# Nixie_Clock.net
KiCad netlist of a schematic drawn in EAGLE
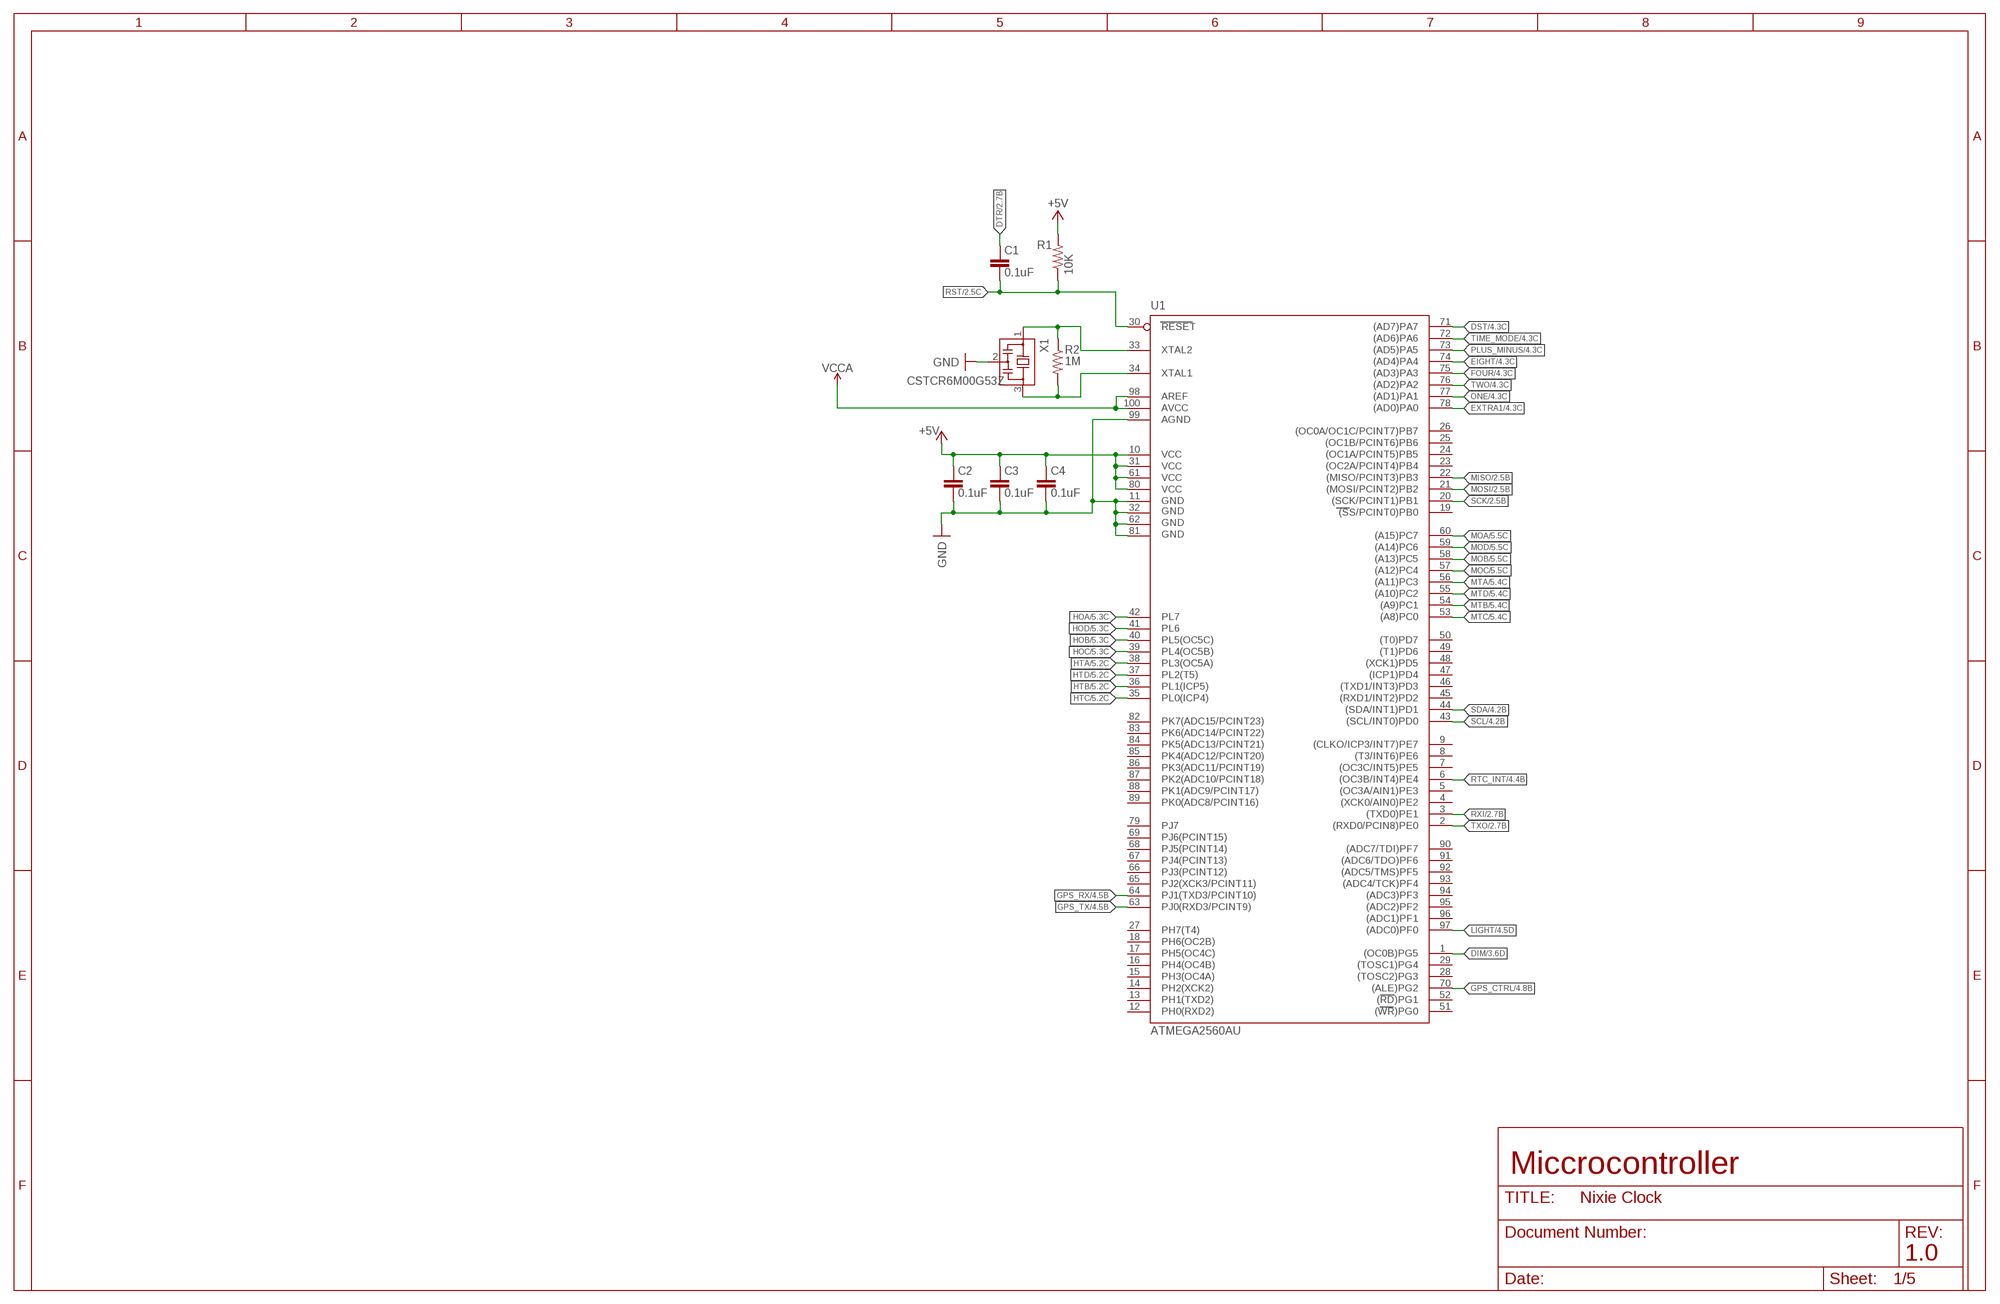
[diagram p0: schematic, sheet 1]
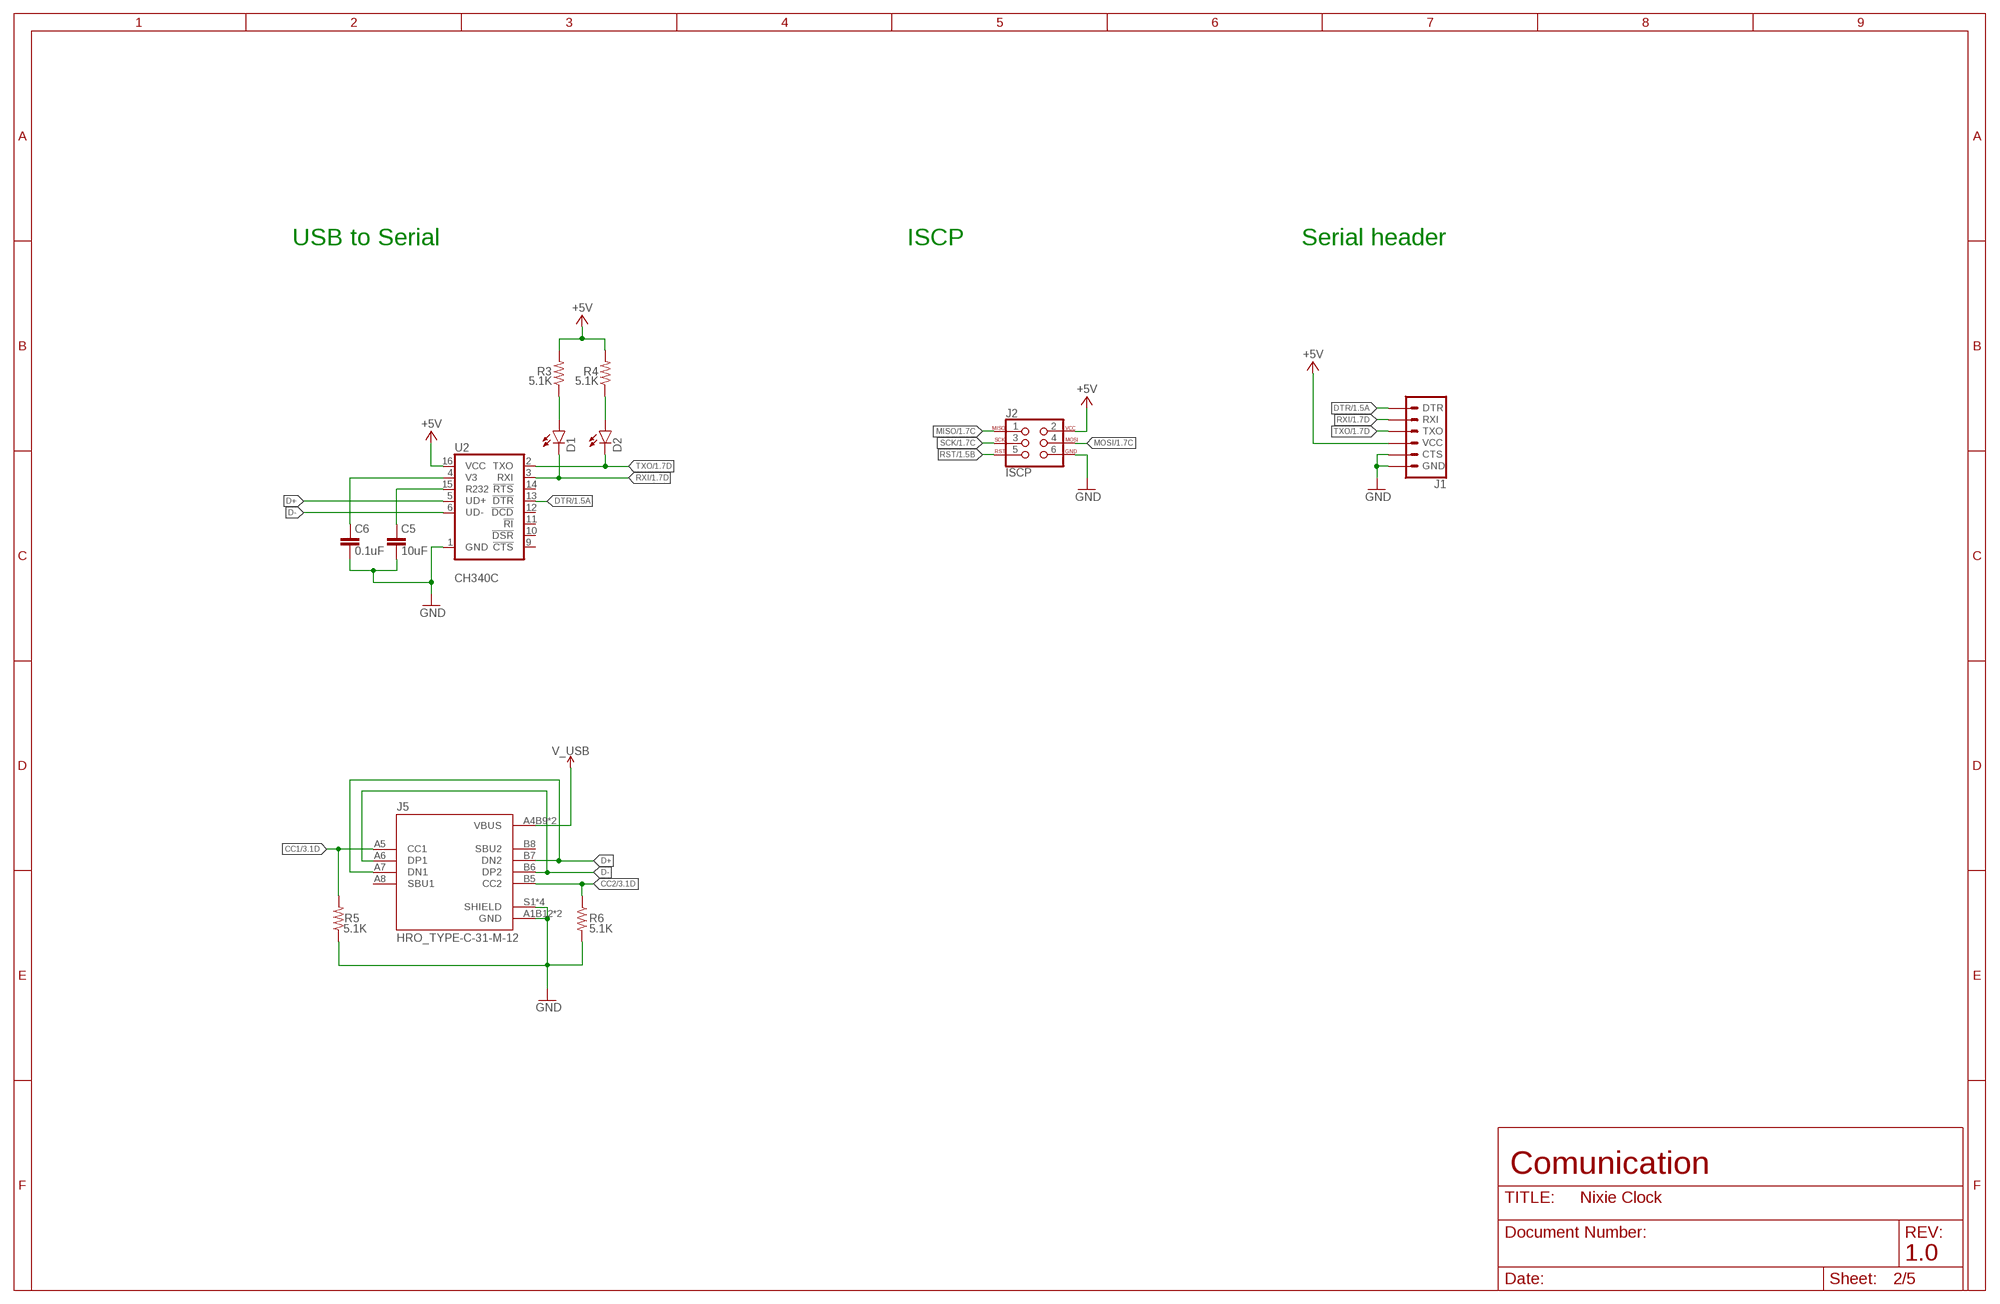
[diagram p1: schematic, sheet 2]
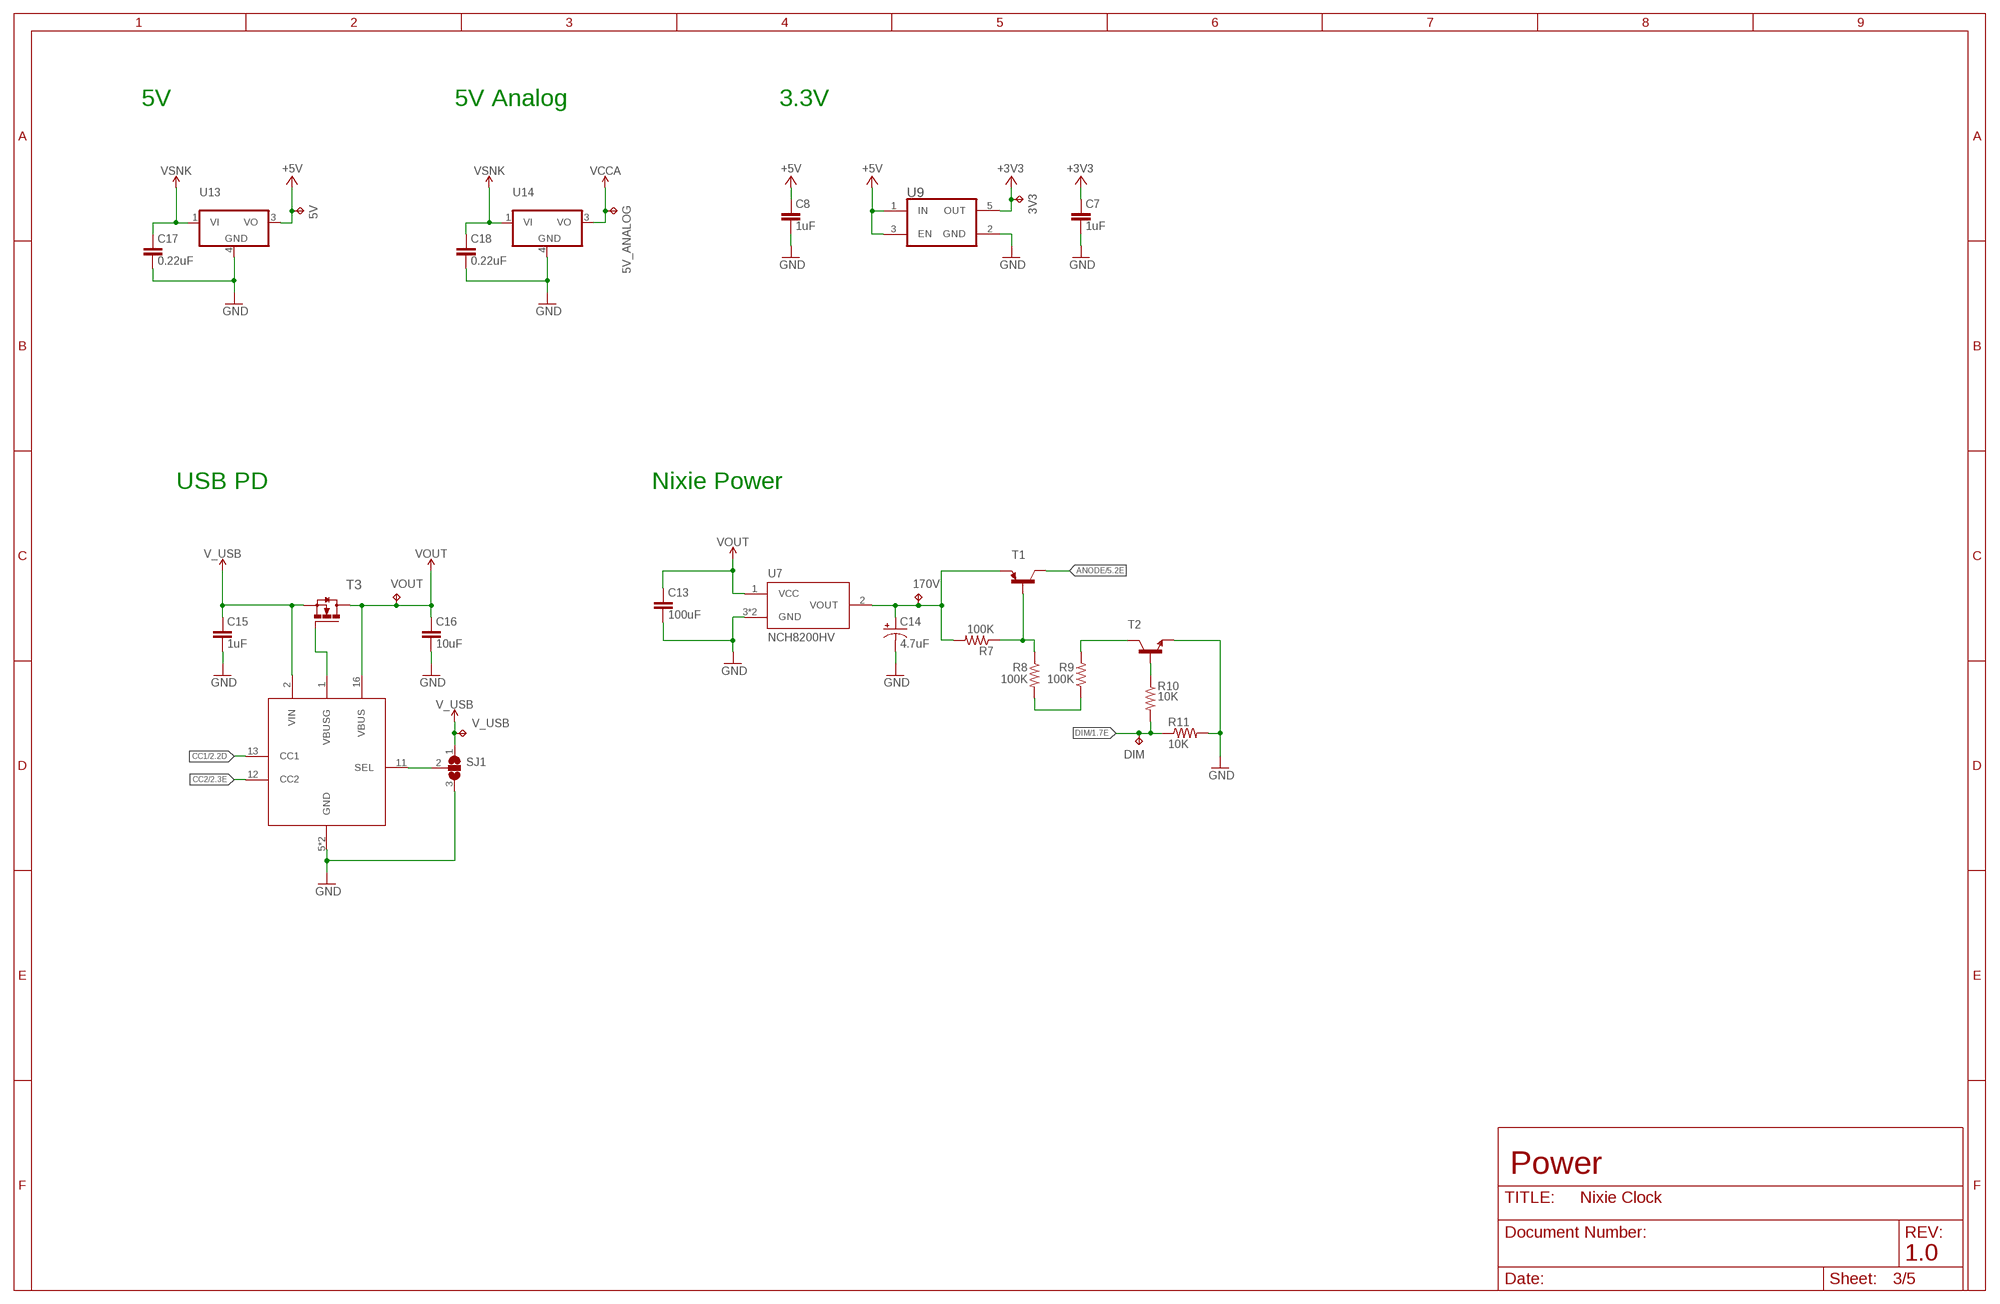
[diagram p2: schematic, sheet 3]
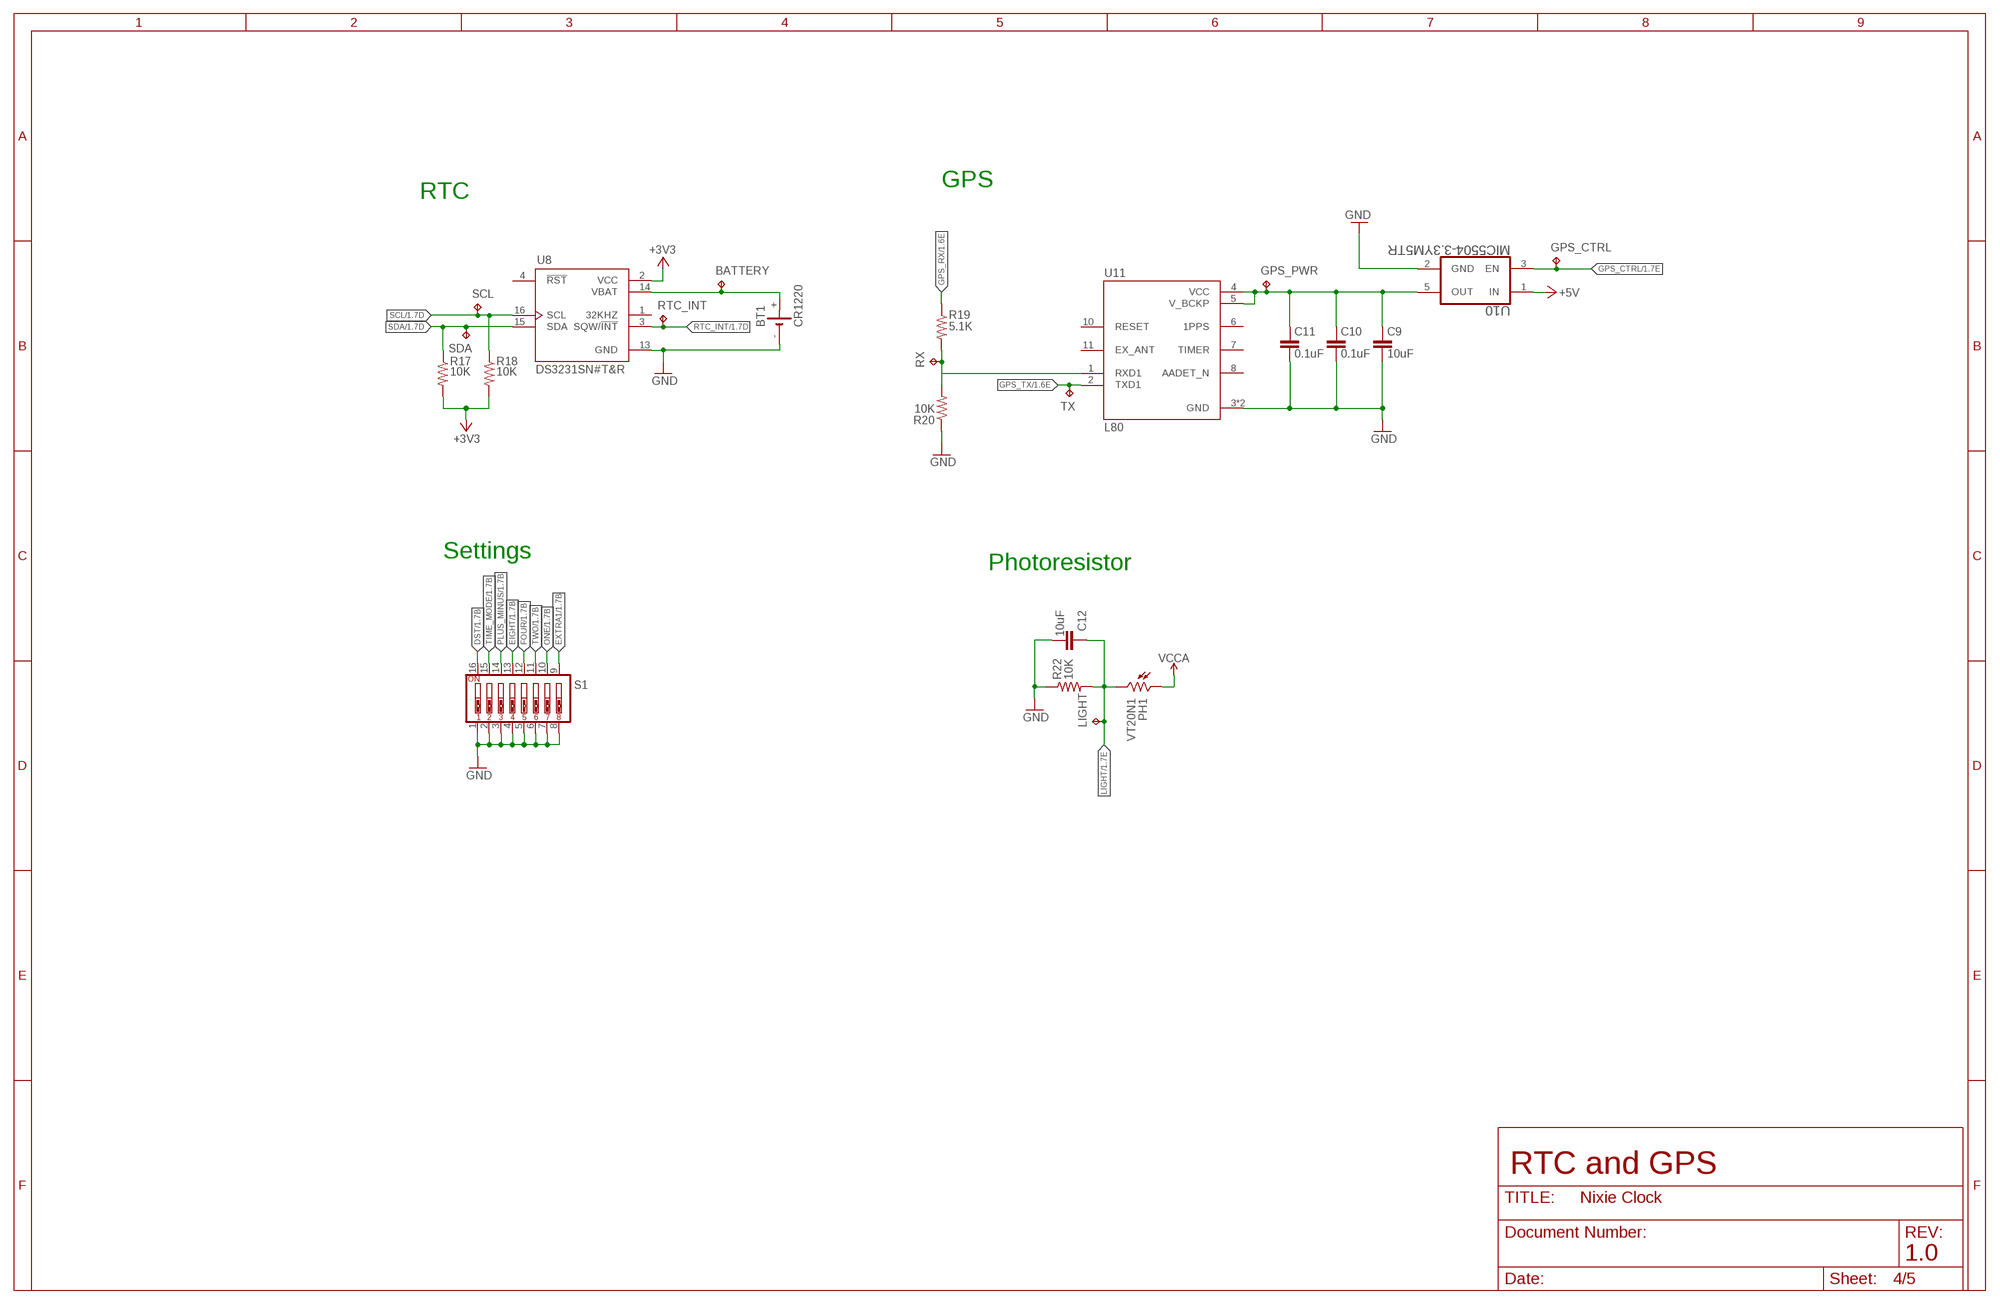
[diagram p3: schematic, sheet 4]
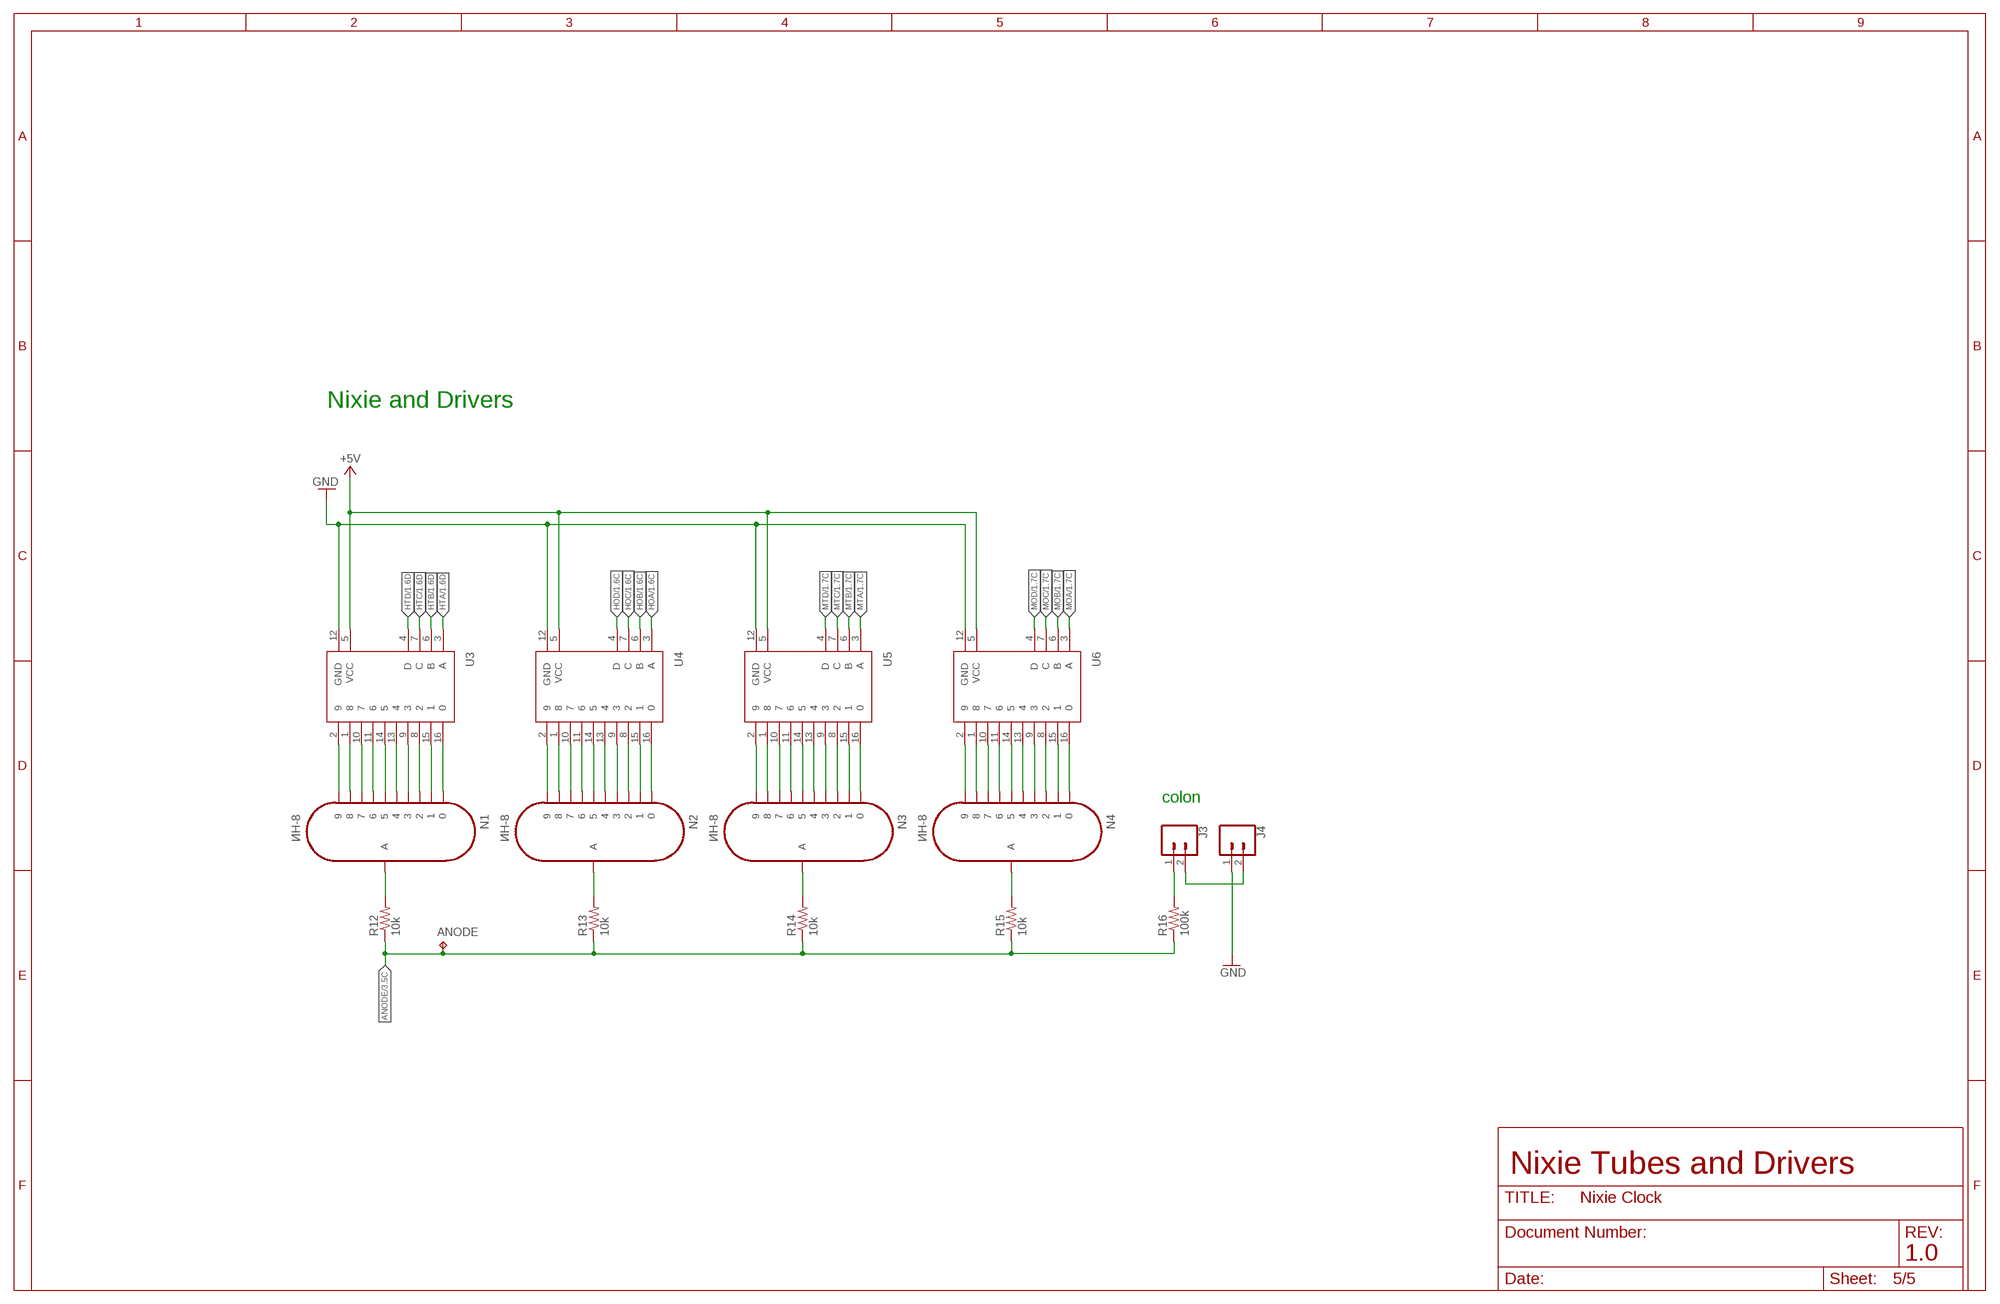
[diagram p4: schematic, sheet 5]

(export (version "E")
  (design (tool "Eeschema 10.0.6"))
  (components
    (comp (ref "BATTERY")
      (value "TPPAD1-13")
      (footprint "eagle-import:P1-13")
      (libsource (lib "eagle-import") (part "TPPAD1-13"))
    )
    (comp (ref "BT1")
      (value "CR1220")
      (footprint "eagle-import:CH291-1220LF")
      (libsource (lib "eagle-import") (part "CH291-1220LF"))
    )
    (comp (ref "C9")
      (value "10uF")
      (footprint "eagle-import:C0603")
      (libsource (lib "eagle-import") (part "C-EUC0603"))
    )
    (comp (ref "C10")
      (value "0.1uF")
      (footprint "eagle-import:C0603")
      (libsource (lib "eagle-import") (part "C-EUC0603"))
    )
    (comp (ref "C11")
      (value "0.1uF")
      (footprint "eagle-import:C0603")
      (libsource (lib "eagle-import") (part "C-EUC0603"))
    )
    (comp (ref "C12")
      (value "10uF")
      (footprint "eagle-import:C0603")
      (libsource (lib "eagle-import") (part "C-EUC0603"))
    )
    (comp (ref "GPS_CTRL")
      (value "TPPAD1-13")
      (footprint "eagle-import:P1-13")
      (libsource (lib "eagle-import") (part "TPPAD1-13"))
    )
    (comp (ref "GPS_PWR")
      (value "TPPAD1-13")
      (footprint "eagle-import:P1-13")
      (libsource (lib "eagle-import") (part "TPPAD1-13"))
    )
    (comp (ref "LIGHT")
      (value "TPPAD1-13")
      (footprint "eagle-import:P1-13")
      (libsource (lib "eagle-import") (part "TPPAD1-13"))
    )
    (comp (ref "PH1")
      (value "VT20N1")
      (footprint "eagle-import:TO46-VT200")
      (libsource (lib "eagle-import") (part "VT20N1"))
    )
    (comp (ref "R17")
      (value "10K")
      (footprint "eagle-import:R0603")
      (libsource (lib "eagle-import") (part "R-US_R0603"))
    )
    (comp (ref "R18")
      (value "10K")
      (footprint "eagle-import:R0603")
      (libsource (lib "eagle-import") (part "R-US_R0603"))
    )
    (comp (ref "R19")
      (value "5.1K")
      (footprint "eagle-import:R0603")
      (libsource (lib "eagle-import") (part "R-US_R0603"))
    )
    (comp (ref "R20")
      (value "10K")
      (footprint "eagle-import:R0603")
      (libsource (lib "eagle-import") (part "R-US_R0603"))
    )
    (comp (ref "R22")
      (value "10K")
      (footprint "eagle-import:R0603")
      (libsource (lib "eagle-import") (part "R-US_R0603"))
    )
    (comp (ref "RTC_INT")
      (value "TPPAD1-13")
      (footprint "eagle-import:P1-13")
      (libsource (lib "eagle-import") (part "TPPAD1-13"))
    )
    (comp (ref "RX")
      (value "TPPAD1-13")
      (footprint "eagle-import:P1-13")
      (libsource (lib "eagle-import") (part "TPPAD1-13"))
    )
    (comp (ref "S1")
      (value "SW_DIP-8")
      (footprint "eagle-import:EDG-08")
      (libsource (lib "eagle-import") (part "SW_DIP-8"))
    )
    (comp (ref "SCL")
      (value "TPPAD1-13")
      (footprint "eagle-import:P1-13")
      (libsource (lib "eagle-import") (part "TPPAD1-13"))
    )
    (comp (ref "SDA")
      (value "TPPAD1-13")
      (footprint "eagle-import:P1-13")
      (libsource (lib "eagle-import") (part "TPPAD1-13"))
    )
    (comp (ref "TX")
      (value "TPPAD1-13")
      (footprint "eagle-import:P1-13")
      (libsource (lib "eagle-import") (part "TPPAD1-13"))
    )
    (comp (ref "U8")
      (value "DS3231SN#T&R")
      (footprint "eagle-import:SOIC127P1032X265-16N")
      (fields (field (name "MF") "Maxim Integrated") (field (name "MP") "DS3231SN#T&amp;R"))
      (libsource (lib "eagle-import") (part "DS3231SN#T&R"))
    )
    (comp (ref "U10")
      (value "MIC5504-3.3YM5TR")
      (footprint "eagle-import:SOT95P280X130-5N")
      (fields (field (name "MPN") "MIC5504-3.3YM5-TR"))
      (libsource (lib "eagle-import") (part "MIC5504-3.3YM5TR"))
    )
    (comp (ref "U11")
      (value "L80")
      (footprint "eagle-import:XCVR_L80")
      (fields (field (name "MF") "Quectel") (field (name "MP") "L80-M39"))
      (libsource (lib "eagle-import") (part "L80"))
    )
    (comp (ref "ANODE")
      (value "TPPAD1-13")
      (footprint "eagle-import:P1-13")
      (libsource (lib "eagle-import") (part "TPPAD1-13"))
    )
    (comp (ref "J3")
      (value "CONN_02LOCK_LONGPADS")
      (footprint "eagle-import:1X02_LOCK_LONGPADS")
      (libsource (lib "eagle-import") (part "CONN_02LOCK_LONGPADS"))
    )
    (comp (ref "J4")
      (value "CONN_02LOCK_LONGPADS")
      (footprint "eagle-import:1X02_LOCK_LONGPADS")
      (libsource (lib "eagle-import") (part "CONN_02LOCK_LONGPADS"))
    )
    (comp (ref "N1")
      (value "ИН-8")
      (footprint "eagle-import:IN-8_SOCKET")
      (libsource (lib "eagle-import") (part "IN-8IN-8_SOCKET"))
    )
    (comp (ref "N2")
      (value "ИН-8")
      (footprint "eagle-import:IN-8_SOCKET")
      (libsource (lib "eagle-import") (part "IN-8IN-8_SOCKET"))
    )
    (comp (ref "N3")
      (value "ИН-8")
      (footprint "eagle-import:IN-8_SOCKET")
      (libsource (lib "eagle-import") (part "IN-8IN-8_SOCKET"))
    )
    (comp (ref "N4")
      (value "ИН-8")
      (footprint "eagle-import:IN-8_SOCKET")
      (libsource (lib "eagle-import") (part "IN-8IN-8_SOCKET"))
    )
    (comp (ref "R12")
      (value "10k")
      (footprint "eagle-import:M0805")
      (libsource (lib "eagle-import") (part "R-US_M0805"))
    )
    (comp (ref "R13")
      (value "10k")
      (footprint "eagle-import:M0805")
      (libsource (lib "eagle-import") (part "R-US_M0805"))
    )
    (comp (ref "R14")
      (value "10k")
      (footprint "eagle-import:M0805")
      (libsource (lib "eagle-import") (part "R-US_M0805"))
    )
    (comp (ref "R15")
      (value "10k")
      (footprint "eagle-import:M0805")
      (libsource (lib "eagle-import") (part "R-US_M0805"))
    )
    (comp (ref "R16")
      (value "100k")
      (footprint "eagle-import:R0603")
      (libsource (lib "eagle-import") (part "R-US_R0603"))
    )
    (comp (ref "U3")
      (value "K155ID1")
      (footprint "eagle-import:DIL16-KIT")
      (libsource (lib "eagle-import") (part "K155ID1"))
    )
    (comp (ref "U4")
      (value "K155ID1")
      (footprint "eagle-import:DIL16-KIT")
      (libsource (lib "eagle-import") (part "K155ID1"))
    )
    (comp (ref "U5")
      (value "K155ID1")
      (footprint "eagle-import:DIL16-KIT")
      (libsource (lib "eagle-import") (part "K155ID1"))
    )
    (comp (ref "U6")
      (value "K155ID1")
      (footprint "eagle-import:DIL16-KIT")
      (libsource (lib "eagle-import") (part "K155ID1"))
    )
    (comp (ref "C5")
      (value "10uF")
      (footprint "eagle-import:C0603")
      (libsource (lib "eagle-import") (part "C-EUC0603"))
    )
    (comp (ref "C6")
      (value "0.1uF")
      (footprint "eagle-import:C0603")
      (libsource (lib "eagle-import") (part "C-EUC0603"))
    )
    (comp (ref "D1")
      (value "LEDCHIP-LED0603")
      (footprint "eagle-import:CHIP-LED0603")
      (libsource (lib "eagle-import") (part "LEDCHIP-LED0603"))
    )
    (comp (ref "D2")
      (value "LEDCHIP-LED0603")
      (footprint "eagle-import:CHIP-LED0603")
      (libsource (lib "eagle-import") (part "LEDCHIP-LED0603"))
    )
    (comp (ref "J1")
      (value "6_PIN_SERIAL_TARGETSILK")
      (footprint "eagle-import:6_PIN_SERIAL_TARGET_SIDE_W_SILK")
      (libsource (lib "eagle-import") (part "6_PIN_SERIAL_TARGETSILK"))
    )
    (comp (ref "J2")
      (value "ISCP")
      (footprint "eagle-import:2X3")
      (libsource (lib "eagle-import") (part "AVR_SPI_PROG_3X2PTH"))
    )
    (comp (ref "J5")
      (value "HRO_TYPE-C-31-M-12")
      (footprint "eagle-import:HRO_TYPE-C-31-M-12")
      (fields (field (name "MF") "HRO Electronics Co., Ltd.") (field (name "MP") "TYPE-C-31-M-12"))
      (libsource (lib "eagle-import") (part "HRO_TYPE-C-31-M-12"))
    )
    (comp (ref "R3")
      (value "5.1K")
      (footprint "eagle-import:R0603")
      (libsource (lib "eagle-import") (part "R-US_R0603"))
    )
    (comp (ref "R4")
      (value "5.1K")
      (footprint "eagle-import:R0603")
      (libsource (lib "eagle-import") (part "R-US_R0603"))
    )
    (comp (ref "R5")
      (value "5.1K")
      (footprint "eagle-import:R0603")
      (libsource (lib "eagle-import") (part "R-US_R0603"))
    )
    (comp (ref "R6")
      (value "5.1K")
      (footprint "eagle-import:R0603")
      (libsource (lib "eagle-import") (part "R-US_R0603"))
    )
    (comp (ref "U2")
      (value "CH340C")
      (footprint "eagle-import:SO016")
      (libsource (lib "eagle-import") (part "CH340C"))
    )
    (comp (ref "3V3")
      (value "TPPAD1-13")
      (footprint "eagle-import:P1-13")
      (libsource (lib "eagle-import") (part "TPPAD1-13"))
    )
    (comp (ref "5V")
      (value "TPPAD1-13")
      (footprint "eagle-import:P1-13")
      (libsource (lib "eagle-import") (part "TPPAD1-13"))
    )
    (comp (ref "5V_ANALOG")
      (value "TPPAD1-13")
      (footprint "eagle-import:P1-13")
      (libsource (lib "eagle-import") (part "TPPAD1-13"))
    )
    (comp (ref "170V")
      (value "TPPAD1-13")
      (footprint "eagle-import:P1-13")
      (libsource (lib "eagle-import") (part "TPPAD1-13"))
    )
    (comp (ref "C7")
      (value "1uF")
      (footprint "eagle-import:C0603")
      (libsource (lib "eagle-import") (part "C-EUC0603"))
    )
    (comp (ref "C8")
      (value "1uF")
      (footprint "eagle-import:C0603")
      (libsource (lib "eagle-import") (part "C-EUC0603"))
    )
    (comp (ref "C13")
      (value "100uF")
      (footprint "eagle-import:C0603")
      (libsource (lib "eagle-import") (part "C-EUC0603"))
    )
    (comp (ref "C14")
      (value "4.7uF")
      (footprint "eagle-import:E3,5-8")
      (libsource (lib "eagle-import") (part "CPOL-USE3.5-8"))
    )
    (comp (ref "C15")
      (value "1uF")
      (footprint "eagle-import:C0603")
      (libsource (lib "eagle-import") (part "C-EUC0603"))
    )
    (comp (ref "C16")
      (value "10uF")
      (footprint "eagle-import:C0603")
      (libsource (lib "eagle-import") (part "C-EUC0603"))
    )
    (comp (ref "C17")
      (value "0.22uF")
      (footprint "eagle-import:C0603")
      (libsource (lib "eagle-import") (part "C-EUC0603"))
    )
    (comp (ref "C18")
      (value "0.22uF")
      (footprint "eagle-import:C0603")
      (libsource (lib "eagle-import") (part "C-EUC0603"))
    )
    (comp (ref "DIM")
      (value "TPPAD1-13")
      (footprint "eagle-import:P1-13")
      (libsource (lib "eagle-import") (part "TPPAD1-13"))
    )
    (comp (ref "R7")
      (value "100K")
      (footprint "eagle-import:R0603")
      (libsource (lib "eagle-import") (part "R-US_R0603"))
    )
    (comp (ref "R8")
      (value "100K")
      (footprint "eagle-import:R0603")
      (libsource (lib "eagle-import") (part "R-US_R0603"))
    )
    (comp (ref "R9")
      (value "100K")
      (footprint "eagle-import:R0603")
      (libsource (lib "eagle-import") (part "R-US_R0603"))
    )
    (comp (ref "R10")
      (value "10K")
      (footprint "eagle-import:R0603")
      (libsource (lib "eagle-import") (part "R-US_R0603"))
    )
    (comp (ref "R11")
      (value "10K")
      (footprint "eagle-import:R0603")
      (libsource (lib "eagle-import") (part "R-US_R0603"))
    )
    (comp (ref "SJ1")
      (value "SJ2W")
      (footprint "eagle-import:SJ_2")
      (libsource (lib "eagle-import") (part "SJ2W"))
    )
    (comp (ref "T1")
      (value "PZTA92")
      (footprint "eagle-import:SOT223")
      (libsource (lib "eagle-import") (part "PZTA92"))
    )
    (comp (ref "T2")
      (value "PZTA42")
      (footprint "eagle-import:SOT223")
      (libsource (lib "eagle-import") (part "PZTA42"))
    )
    (comp (ref "T3")
      (value "CSD18543Q3A")
      (footprint "eagle-import:VSONP-8")
      (fields (field (name "MFR") "TI"))
      (libsource (lib "eagle-import") (part "CSD18543Q3A"))
    )
    (comp (ref "U7")
      (value "NCH8200HV")
      (footprint "eagle-import:NCH8200HV")
      (libsource (lib "eagle-import") (part "NCH8200HV"))
    )
    (comp (ref "U9")
      (value "MIC5504-3.3YM5TR")
      (footprint "eagle-import:SOT95P280X130-5N")
      (fields (field (name "MPN") "MIC5504-3.3YM5-TR"))
      (libsource (lib "eagle-import") (part "MIC5504-3.3YM5TR"))
    )
    (comp (ref "U12")
      (value "IP2721")
      (footprint "eagle-import:TSSOP16EXP")
      (libsource (lib "eagle-import") (part "IP2721"))
    )
    (comp (ref "U13")
      (value "LM340MP-05")
      (footprint "eagle-import:SOT223")
      (fields (field (name "MFR") "TI") (field (name "MPN") "LM340MP-5.0/NOPB"))
      (libsource (lib "eagle-import") (part "LM340?-MP05"))
    )
    (comp (ref "U14")
      (value "LM340MP-05")
      (footprint "eagle-import:SOT223")
      (libsource (lib "eagle-import") (part "LM340?-MP05"))
    )
    (comp (ref "VOUT")
      (value "TPPAD1-13")
      (footprint "eagle-import:P1-13")
      (libsource (lib "eagle-import") (part "TPPAD1-13"))
    )
    (comp (ref "V_USB")
      (value "TPPAD1-13")
      (footprint "eagle-import:P1-13")
      (libsource (lib "eagle-import") (part "TPPAD1-13"))
    )
    (comp (ref "C1")
      (value "0.1uF")
      (footprint "eagle-import:C0603")
      (libsource (lib "eagle-import") (part "C-EUC0603"))
    )
    (comp (ref "C2")
      (value "0.1uF")
      (footprint "eagle-import:C0603")
      (libsource (lib "eagle-import") (part "C-EUC0603"))
    )
    (comp (ref "C3")
      (value "0.1uF")
      (footprint "eagle-import:C0603")
      (libsource (lib "eagle-import") (part "C-EUC0603"))
    )
    (comp (ref "C4")
      (value "0.1uF")
      (footprint "eagle-import:C0603")
      (libsource (lib "eagle-import") (part "C-EUC0603"))
    )
    (comp (ref "R1")
      (value "10K")
      (footprint "eagle-import:R0603")
      (libsource (lib "eagle-import") (part "R-US_R0603"))
    )
    (comp (ref "R2")
      (value "1M")
      (footprint "eagle-import:R0603")
      (libsource (lib "eagle-import") (part "R-US_R0603"))
    )
    (comp (ref "U1")
      (value "ATMEGA2560AU")
      (footprint "eagle-import:TQFP100")
      (fields (field (name "MPN") "ATMEGA2560-16AU"))
      (libsource (lib "eagle-import") (part "ATMEGA2560AU"))
    )
    (comp (ref "X1")
      (value "CSTCR6M00G53Z")
      (footprint "eagle-import:CSTCR6M")
      (fields (field (name "MPN") "CSTCR6M00G53-R0") (field (name "MPN_1") "CSTCE16M0V13C99-R0"))
      (libsource (lib "eagle-import") (part "CSTCR6M00G53Z"))
    )
  )
  (nets
    (net (code "1") (name "+3V3") (class "Default")
      (node (ref "3V3") (pin "TP") (pinfunction "TP_TP") (pintype "input"))
      (node (ref "C7") (pin "1") (pinfunction "1_1") (pintype "passive"))
      (node (ref "R17") (pin "2") (pinfunction "2_2") (pintype "passive"))
      (node (ref "R18") (pin "2") (pinfunction "2_2") (pintype "passive"))
      (node (ref "U8") (pin "2") (pinfunction "VCC_2") (pintype "power_in"))
      (node (ref "U9") (pin "5") (pinfunction "OUT_5") (pintype "output"))
    )
    (net (code "2") (name "+5V") (class "Default")
      (node (ref "5V") (pin "TP") (pinfunction "TP_TP") (pintype "input"))
      (node (ref "C2") (pin "1") (pinfunction "1_1") (pintype "passive"))
      (node (ref "C3") (pin "1") (pinfunction "1_1") (pintype "passive"))
      (node (ref "C4") (pin "1") (pinfunction "1_1") (pintype "passive"))
      (node (ref "C8") (pin "1") (pinfunction "1_1") (pintype "passive"))
      (node (ref "J1") (pin "P$4") (pinfunction "VCC_P$4") (pintype "passive"))
      (node (ref "J2") (pin "2") (pinfunction "2_2") (pintype "passive"))
      (node (ref "R1") (pin "2") (pinfunction "2_2") (pintype "passive"))
      (node (ref "R3") (pin "2") (pinfunction "2_2") (pintype "passive"))
      (node (ref "R4") (pin "2") (pinfunction "2_2") (pintype "passive"))
      (node (ref "U1") (pin "10") (pinfunction "VCC_10") (pintype "power_in"))
      (node (ref "U1") (pin "31") (pinfunction "VCC1_31") (pintype "power_in"))
      (node (ref "U1") (pin "61") (pinfunction "VCC2_61") (pintype "power_in"))
      (node (ref "U1") (pin "80") (pinfunction "VCC3_80") (pintype "power_in"))
      (node (ref "U10") (pin "1") (pinfunction "IN_1") (pintype "input"))
      (node (ref "U13") (pin "3") (pinfunction "VO_3") (pintype "passive"))
      (node (ref "U2") (pin "16") (pinfunction "VCC_16") (pintype "bidirectional"))
      (node (ref "U3") (pin "5") (pinfunction "VCC_5") (pintype "bidirectional"))
      (node (ref "U4") (pin "5") (pinfunction "VCC_5") (pintype "bidirectional"))
      (node (ref "U5") (pin "5") (pinfunction "VCC_5") (pintype "bidirectional"))
      (node (ref "U6") (pin "5") (pinfunction "VCC_5") (pintype "bidirectional"))
      (node (ref "U9") (pin "1") (pinfunction "IN_1") (pintype "input"))
      (node (ref "U9") (pin "3") (pinfunction "EN_3") (pintype "input"))
    )
    (net (code "3") (name "ANODE") (class "Default")
      (node (ref "ANODE") (pin "TP") (pinfunction "TP_TP") (pintype "input"))
      (node (ref "R12") (pin "1") (pinfunction "1_1") (pintype "passive"))
      (node (ref "R13") (pin "1") (pinfunction "1_1") (pintype "passive"))
      (node (ref "R14") (pin "1") (pinfunction "1_1") (pintype "passive"))
      (node (ref "R15") (pin "1") (pinfunction "1_1") (pintype "passive"))
      (node (ref "R16") (pin "1") (pinfunction "1_1") (pintype "passive"))
      (node (ref "T1") (pin "2") (pinfunction "C_2") (pintype "passive"))
      (node (ref "T1") (pin "4") (pinfunction "C_4") (pintype "passive"))
    )
    (net (code "4") (name "CC1") (class "Default")
      (node (ref "J5") (pin "A5") (pinfunction "CC1_A5") (pintype "bidirectional"))
      (node (ref "R5") (pin "2") (pinfunction "2_2") (pintype "passive"))
      (node (ref "U12") (pin "13") (pinfunction "CC1_13") (pintype "bidirectional"))
    )
    (net (code "5") (name "CC2") (class "Default")
      (node (ref "J5") (pin "B5") (pinfunction "CC2_B5") (pintype "bidirectional"))
      (node (ref "R6") (pin "1") (pinfunction "1_1") (pintype "passive"))
      (node (ref "U12") (pin "12") (pinfunction "CC2_12") (pintype "bidirectional"))
    )
    (net (code "6") (name "D+") (class "Default")
      (node (ref "J5") (pin "A7") (pinfunction "DN1_A7") (pintype "bidirectional"))
      (node (ref "J5") (pin "B7") (pinfunction "DN2_B7") (pintype "bidirectional"))
      (node (ref "U2") (pin "5") (pinfunction "UD+_5") (pintype "bidirectional"))
    )
    (net (code "7") (name "D-") (class "Default")
      (node (ref "J5") (pin "A6") (pinfunction "DP1_A6") (pintype "bidirectional"))
      (node (ref "J5") (pin "B6") (pinfunction "DP2_B6") (pintype "bidirectional"))
      (node (ref "U2") (pin "6") (pinfunction "UD-_6") (pintype "bidirectional"))
    )
    (net (code "8") (name "DIM") (class "Default")
      (node (ref "DIM") (pin "TP") (pinfunction "TP_TP") (pintype "input"))
      (node (ref "R10") (pin "2") (pinfunction "2_2") (pintype "passive"))
      (node (ref "R11") (pin "1") (pinfunction "1_1") (pintype "passive"))
      (node (ref "U1") (pin "1") (pinfunction "(OC0B)PG5_1") (pintype "bidirectional"))
    )
    (net (code "9") (name "DST") (class "Default")
      (node (ref "S1") (pin "16") (pinfunction "16_16") (pintype "passive"))
      (node (ref "U1") (pin "71") (pinfunction "(AD7)PA7_71") (pintype "bidirectional"))
    )
    (net (code "10") (name "DTR") (class "Default")
      (node (ref "C1") (pin "1") (pinfunction "1_1") (pintype "passive"))
      (node (ref "J1") (pin "P$1") (pinfunction "DTR_P$1") (pintype "passive"))
      (node (ref "U2") (pin "13") (pinfunction "~{DTR}_13") (pintype "bidirectional"))
    )
    (net (code "11") (name "EIGHT") (class "Default")
      (node (ref "S1") (pin "13") (pinfunction "13_13") (pintype "passive"))
      (node (ref "U1") (pin "74") (pinfunction "(AD4)PA4_74") (pintype "bidirectional"))
    )
    (net (code "12") (name "EXTRA1") (class "Default")
      (node (ref "S1") (pin "9") (pinfunction "9_9") (pintype "passive"))
      (node (ref "U1") (pin "78") (pinfunction "(AD0)PA0_78") (pintype "bidirectional"))
    )
    (net (code "13") (name "FOUR") (class "Default")
      (node (ref "S1") (pin "12") (pinfunction "12_12") (pintype "passive"))
      (node (ref "U1") (pin "75") (pinfunction "(AD3)PA3_75") (pintype "bidirectional"))
    )
    (net (code "14") (name "GND") (class "Default")
      (node (ref "BT1") (pin "-") (pinfunction "-_-") (pintype "passive"))
      (node (ref "C10") (pin "2") (pinfunction "2_2") (pintype "passive"))
      (node (ref "C11") (pin "2") (pinfunction "2_2") (pintype "passive"))
      (node (ref "C12") (pin "2") (pinfunction "2_2") (pintype "passive"))
      (node (ref "C13") (pin "2") (pinfunction "2_2") (pintype "passive"))
      (node (ref "C14") (pin "-") (pinfunction "-_-") (pintype "passive"))
      (node (ref "C15") (pin "2") (pinfunction "2_2") (pintype "passive"))
      (node (ref "C16") (pin "2") (pinfunction "2_2") (pintype "passive"))
      (node (ref "C17") (pin "2") (pinfunction "2_2") (pintype "passive"))
      (node (ref "C18") (pin "2") (pinfunction "2_2") (pintype "passive"))
      (node (ref "C2") (pin "2") (pinfunction "2_2") (pintype "passive"))
      (node (ref "C3") (pin "2") (pinfunction "2_2") (pintype "passive"))
      (node (ref "C4") (pin "2") (pinfunction "2_2") (pintype "passive"))
      (node (ref "C5") (pin "2") (pinfunction "2_2") (pintype "passive"))
      (node (ref "C6") (pin "2") (pinfunction "2_2") (pintype "passive"))
      (node (ref "C7") (pin "2") (pinfunction "2_2") (pintype "passive"))
      (node (ref "C8") (pin "2") (pinfunction "2_2") (pintype "passive"))
      (node (ref "C9") (pin "2") (pinfunction "2_2") (pintype "passive"))
      (node (ref "J1") (pin "P$5") (pinfunction "CTS_P$5") (pintype "passive"))
      (node (ref "J1") (pin "P$6") (pinfunction "GND_P$6") (pintype "passive"))
      (node (ref "J2") (pin "6") (pinfunction "6_6") (pintype "passive"))
      (node (ref "J4") (pin "1") (pinfunction "1_1") (pintype "passive"))
      (node (ref "J5") (pin "A1B12") (pinfunction "GND_A1B12") (pintype "power_in"))
      (node (ref "J5") (pin "B1A12") (pinfunction "GND_B1A12") (pintype "power_in"))
      (node (ref "J5") (pin "S1") (pinfunction "SHIELD_S1") (pintype "passive"))
      (node (ref "J5") (pin "S2") (pinfunction "SHIELD_S2") (pintype "passive"))
      (node (ref "J5") (pin "S3") (pinfunction "SHIELD_S3") (pintype "passive"))
      (node (ref "J5") (pin "S4") (pinfunction "SHIELD_S4") (pintype "passive"))
      (node (ref "R11") (pin "2") (pinfunction "2_2") (pintype "passive"))
      (node (ref "R20") (pin "1") (pinfunction "1_1") (pintype "passive"))
      (node (ref "R22") (pin "1") (pinfunction "1_1") (pintype "passive"))
      (node (ref "R5") (pin "1") (pinfunction "1_1") (pintype "passive"))
      (node (ref "R6") (pin "2") (pinfunction "2_2") (pintype "passive"))
      (node (ref "S1") (pin "1") (pinfunction "1_1") (pintype "passive"))
      (node (ref "S1") (pin "2") (pinfunction "2_2") (pintype "passive"))
      (node (ref "S1") (pin "3") (pinfunction "3_3") (pintype "passive"))
      (node (ref "S1") (pin "4") (pinfunction "4_4") (pintype "passive"))
      (node (ref "S1") (pin "5") (pinfunction "5_5") (pintype "passive"))
      (node (ref "S1") (pin "6") (pinfunction "6_6") (pintype "passive"))
      (node (ref "S1") (pin "7") (pinfunction "7_7") (pintype "passive"))
      (node (ref "S1") (pin "8") (pinfunction "8_8") (pintype "passive"))
      (node (ref "SJ1") (pin "3") (pinfunction "3_3") (pintype "passive"))
      (node (ref "T2") (pin "3") (pinfunction "E_3") (pintype "passive"))
      (node (ref "U1") (pin "11") (pinfunction "GND_11") (pintype "power_in"))
      (node (ref "U1") (pin "32") (pinfunction "GND1_32") (pintype "power_in"))
      (node (ref "U1") (pin "62") (pinfunction "GND2_62") (pintype "power_in"))
      (node (ref "U1") (pin "81") (pinfunction "GND3_81") (pintype "power_in"))
      (node (ref "U1") (pin "99") (pinfunction "AGND_99") (pintype "power_in"))
      (node (ref "U10") (pin "2") (pinfunction "GND_2") (pintype "passive"))
      (node (ref "U11") (pin "12") (pinfunction "GND_12") (pintype "power_in"))
      (node (ref "U11") (pin "3") (pinfunction "GND_3") (pintype "power_in"))
      (node (ref "U12") (pin "5") (pinfunction "GND_5") (pintype "bidirectional"))
      (node (ref "U12") (pin "EXP") (pinfunction "GND_EXP") (pintype "bidirectional"))
      (node (ref "U13") (pin "4") (pinfunction "GND_4") (pintype "passive"))
      (node (ref "U14") (pin "4") (pinfunction "GND_4") (pintype "passive"))
      (node (ref "U2") (pin "1") (pinfunction "GND_1") (pintype "bidirectional"))
      (node (ref "U3") (pin "12") (pinfunction "GND_12") (pintype "bidirectional"))
      (node (ref "U4") (pin "12") (pinfunction "GND_12") (pintype "bidirectional"))
      (node (ref "U5") (pin "12") (pinfunction "GND_12") (pintype "bidirectional"))
      (node (ref "U6") (pin "12") (pinfunction "GND_12") (pintype "bidirectional"))
      (node (ref "U7") (pin "3") (pinfunction "GND_3") (pintype "bidirectional"))
      (node (ref "U7") (pin "4") (pinfunction "GND_4") (pintype "bidirectional"))
      (node (ref "U8") (pin "13") (pinfunction "GND_13") (pintype "power_in"))
      (node (ref "U9") (pin "2") (pinfunction "GND_2") (pintype "passive"))
      (node (ref "X1") (pin "2") (pinfunction "2_2") (pintype "passive"))
    )
    (net (code "15") (name "GPS_CTRL") (class "Default")
      (node (ref "GPS_CTRL") (pin "TP") (pinfunction "TP_TP") (pintype "input"))
      (node (ref "U1") (pin "70") (pinfunction "(ALE)PG2_70") (pintype "bidirectional"))
      (node (ref "U10") (pin "3") (pinfunction "EN_3") (pintype "input"))
    )
    (net (code "16") (name "GPS_RX") (class "Default")
      (node (ref "R19") (pin "1") (pinfunction "1_1") (pintype "passive"))
      (node (ref "U1") (pin "64") (pinfunction "PJ1(TXD3/PCINT10)_64") (pintype "bidirectional"))
    )
    (net (code "17") (name "GPS_TX") (class "Default")
      (node (ref "TX") (pin "TP") (pinfunction "TP_TP") (pintype "input"))
      (node (ref "U1") (pin "63") (pinfunction "PJ0(RXD3/PCINT9)_63") (pintype "bidirectional"))
      (node (ref "U11") (pin "2") (pinfunction "TXD1_2") (pintype "output"))
    )
    (net (code "18") (name "HOA") (class "Default")
      (node (ref "U1") (pin "42") (pinfunction "PL7_42") (pintype "bidirectional"))
      (node (ref "U4") (pin "3") (pinfunction "A_3") (pintype "input"))
    )
    (net (code "19") (name "HOB") (class "Default")
      (node (ref "U1") (pin "40") (pinfunction "PL5(OC5C)_40") (pintype "bidirectional"))
      (node (ref "U4") (pin "6") (pinfunction "B_6") (pintype "input"))
    )
    (net (code "20") (name "HOC") (class "Default")
      (node (ref "U1") (pin "39") (pinfunction "PL4(OC5B)_39") (pintype "bidirectional"))
      (node (ref "U4") (pin "7") (pinfunction "C_7") (pintype "input"))
    )
    (net (code "21") (name "HOD") (class "Default")
      (node (ref "U1") (pin "41") (pinfunction "PL6_41") (pintype "bidirectional"))
      (node (ref "U4") (pin "4") (pinfunction "D_4") (pintype "input"))
    )
    (net (code "22") (name "HTA") (class "Default")
      (node (ref "U1") (pin "38") (pinfunction "PL3(OC5A)_38") (pintype "bidirectional"))
      (node (ref "U3") (pin "3") (pinfunction "A_3") (pintype "input"))
    )
    (net (code "23") (name "HTB") (class "Default")
      (node (ref "U1") (pin "36") (pinfunction "PL1(ICP5)_36") (pintype "bidirectional"))
      (node (ref "U3") (pin "6") (pinfunction "B_6") (pintype "input"))
    )
    (net (code "24") (name "HTC") (class "Default")
      (node (ref "U1") (pin "35") (pinfunction "PL0(ICP4)_35") (pintype "bidirectional"))
      (node (ref "U3") (pin "7") (pinfunction "C_7") (pintype "input"))
    )
    (net (code "25") (name "HTD") (class "Default")
      (node (ref "U1") (pin "37") (pinfunction "PL2(T5)_37") (pintype "bidirectional"))
      (node (ref "U3") (pin "4") (pinfunction "D_4") (pintype "input"))
    )
    (net (code "26") (name "LIGHT") (class "Default")
      (node (ref "C12") (pin "1") (pinfunction "1_1") (pintype "passive"))
      (node (ref "LIGHT") (pin "TP") (pinfunction "TP_TP") (pintype "input"))
      (node (ref "PH1") (pin "2") (pinfunction "2_2") (pintype "passive"))
      (node (ref "R22") (pin "2") (pinfunction "2_2") (pintype "passive"))
      (node (ref "U1") (pin "97") (pinfunction "(ADC0)PF0_97") (pintype "bidirectional"))
    )
    (net (code "27") (name "MISO") (class "Default")
      (node (ref "J2") (pin "1") (pinfunction "1_1") (pintype "passive"))
      (node (ref "U1") (pin "22") (pinfunction "(MISO/PCINT3)PB3_22") (pintype "bidirectional"))
    )
    (net (code "28") (name "MOA") (class "Default")
      (node (ref "U1") (pin "60") (pinfunction "(A15)PC7_60") (pintype "bidirectional"))
      (node (ref "U6") (pin "3") (pinfunction "A_3") (pintype "input"))
    )
    (net (code "29") (name "MOB") (class "Default")
      (node (ref "U1") (pin "58") (pinfunction "(A13)PC5_58") (pintype "bidirectional"))
      (node (ref "U6") (pin "6") (pinfunction "B_6") (pintype "input"))
    )
    (net (code "30") (name "MOC") (class "Default")
      (node (ref "U1") (pin "57") (pinfunction "(A12)PC4_57") (pintype "bidirectional"))
      (node (ref "U6") (pin "7") (pinfunction "C_7") (pintype "input"))
    )
    (net (code "31") (name "MOD") (class "Default")
      (node (ref "U1") (pin "59") (pinfunction "(A14)PC6_59") (pintype "bidirectional"))
      (node (ref "U6") (pin "4") (pinfunction "D_4") (pintype "input"))
    )
    (net (code "32") (name "MOSI") (class "Default")
      (node (ref "J2") (pin "4") (pinfunction "4_4") (pintype "passive"))
      (node (ref "U1") (pin "21") (pinfunction "(MOSI/PCINT2)PB2_21") (pintype "bidirectional"))
    )
    (net (code "33") (name "MTA") (class "Default")
      (node (ref "U1") (pin "56") (pinfunction "(A11)PC3_56") (pintype "bidirectional"))
      (node (ref "U5") (pin "3") (pinfunction "A_3") (pintype "input"))
    )
    (net (code "34") (name "MTB") (class "Default")
      (node (ref "U1") (pin "54") (pinfunction "(A9)PC1_54") (pintype "bidirectional"))
      (node (ref "U5") (pin "6") (pinfunction "B_6") (pintype "input"))
    )
    (net (code "35") (name "MTC") (class "Default")
      (node (ref "U1") (pin "53") (pinfunction "(A8)PC0_53") (pintype "bidirectional"))
      (node (ref "U5") (pin "7") (pinfunction "C_7") (pintype "input"))
    )
    (net (code "36") (name "MTD") (class "Default")
      (node (ref "U1") (pin "55") (pinfunction "(A10)PC2_55") (pintype "bidirectional"))
      (node (ref "U5") (pin "4") (pinfunction "D_4") (pintype "input"))
    )
    (net (code "37") (name "Net-(D1-PadA)") (class "Default")
      (node (ref "D1") (pin "A") (pinfunction "A_A") (pintype "passive"))
      (node (ref "R3") (pin "1") (pinfunction "1_1") (pintype "passive"))
    )
    (net (code "38") (name "Net-(D2-PadA)") (class "Default")
      (node (ref "D2") (pin "A") (pinfunction "A_A") (pintype "passive"))
      (node (ref "R4") (pin "1") (pinfunction "1_1") (pintype "passive"))
    )
    (net (code "39") (name "Net-(J3-Pad1)") (class "Default")
      (node (ref "J3") (pin "1") (pinfunction "1_1") (pintype "passive"))
      (node (ref "R16") (pin "2") (pinfunction "2_2") (pintype "passive"))
    )
    (net (code "40") (name "Net-(J3-Pad2)") (class "Default")
      (node (ref "J3") (pin "2") (pinfunction "2_2") (pintype "passive"))
      (node (ref "J4") (pin "2") (pinfunction "2_2") (pintype "passive"))
    )
    (net (code "41") (name "Net-(N1-PadA)") (class "Default")
      (node (ref "N1") (pin "A") (pinfunction "A_A") (pintype "bidirectional"))
      (node (ref "R12") (pin "2") (pinfunction "2_2") (pintype "passive"))
    )
    (net (code "42") (name "Net-(N2-PadA)") (class "Default")
      (node (ref "N2") (pin "A") (pinfunction "A_A") (pintype "bidirectional"))
      (node (ref "R13") (pin "2") (pinfunction "2_2") (pintype "passive"))
    )
    (net (code "43") (name "Net-(N3-PadA)") (class "Default")
      (node (ref "N3") (pin "A") (pinfunction "A_A") (pintype "bidirectional"))
      (node (ref "R14") (pin "2") (pinfunction "2_2") (pintype "passive"))
    )
    (net (code "44") (name "Net-(N4-PadA)") (class "Default")
      (node (ref "N4") (pin "A") (pinfunction "A_A") (pintype "bidirectional"))
      (node (ref "R15") (pin "2") (pinfunction "2_2") (pintype "passive"))
    )
    (net (code "45") (name "Net-(R8-Pad2)") (class "Default")
      (node (ref "R8") (pin "2") (pinfunction "2_2") (pintype "passive"))
      (node (ref "R9") (pin "1") (pinfunction "1_1") (pintype "passive"))
    )
    (net (code "46") (name "Net-(R9-Pad2)") (class "Default")
      (node (ref "R9") (pin "2") (pinfunction "2_2") (pintype "passive"))
      (node (ref "T2") (pin "2") (pinfunction "C_2") (pintype "passive"))
      (node (ref "T2") (pin "4") (pinfunction "C_4") (pintype "passive"))
    )
    (net (code "47") (name "Net-(T1-B)") (class "Default")
      (node (ref "R7") (pin "1") (pinfunction "1_1") (pintype "passive"))
      (node (ref "R8") (pin "1") (pinfunction "1_1") (pintype "passive"))
      (node (ref "T1") (pin "1") (pinfunction "B_1") (pintype "passive"))
    )
    (net (code "48") (name "Net-(T1-E)") (class "Default")
      (node (ref "170V") (pin "TP") (pinfunction "TP_TP") (pintype "input"))
      (node (ref "C14") (pin "+") (pinfunction "+_+") (pintype "passive"))
      (node (ref "R7") (pin "2") (pinfunction "2_2") (pintype "passive"))
      (node (ref "T1") (pin "3") (pinfunction "E_3") (pintype "passive"))
      (node (ref "U7") (pin "2") (pinfunction "VOUT_2") (pintype "bidirectional"))
    )
    (net (code "49") (name "Net-(T2-B)") (class "Default")
      (node (ref "R10") (pin "1") (pinfunction "1_1") (pintype "passive"))
      (node (ref "T2") (pin "1") (pinfunction "B_1") (pintype "passive"))
    )
    (net (code "50") (name "Net-(T3-G)") (class "Default")
      (node (ref "T3") (pin "4") (pinfunction "G_4") (pintype "passive"))
      (node (ref "U12") (pin "1") (pinfunction "VBUSG_1") (pintype "bidirectional"))
    )
    (net (code "51") (name "Net-(U1-XTAL1)") (class "Default")
      (node (ref "R2") (pin "2") (pinfunction "2_2") (pintype "passive"))
      (node (ref "U1") (pin "34") (pinfunction "XTAL1_34") (pintype "input"))
      (node (ref "X1") (pin "3") (pinfunction "3_3") (pintype "passive"))
    )
    (net (code "52") (name "Net-(U1-XTAL2)") (class "Default")
      (node (ref "R2") (pin "1") (pinfunction "1_1") (pintype "passive"))
      (node (ref "U1") (pin "33") (pinfunction "XTAL2_33") (pintype "output"))
      (node (ref "X1") (pin "1") (pinfunction "1_1") (pintype "passive"))
    )
    (net (code "53") (name "Net-(U2-R232)") (class "Default")
      (node (ref "C5") (pin "1") (pinfunction "1_1") (pintype "passive"))
      (node (ref "U2") (pin "15") (pinfunction "R232_15") (pintype "bidirectional"))
    )
    (net (code "54") (name "Net-(U2-V3)") (class "Default")
      (node (ref "C6") (pin "1") (pinfunction "1_1") (pintype "passive"))
      (node (ref "U2") (pin "4") (pinfunction "V3_4") (pintype "bidirectional"))
    )
    (net (code "55") (name "Net-(U3-0)") (class "Default")
      (node (ref "N1") (pin "0") (pinfunction "0_0") (pintype "bidirectional"))
      (node (ref "U3") (pin "16") (pinfunction "0_16") (pintype "bidirectional"))
    )
    (net (code "56") (name "Net-(U3-1)") (class "Default")
      (node (ref "N1") (pin "1") (pinfunction "1_1") (pintype "bidirectional"))
      (node (ref "U3") (pin "15") (pinfunction "1_15") (pintype "bidirectional"))
    )
    (net (code "57") (name "Net-(U3-2)") (class "Default")
      (node (ref "N1") (pin "2") (pinfunction "2_2") (pintype "bidirectional"))
      (node (ref "U3") (pin "8") (pinfunction "2_8") (pintype "bidirectional"))
    )
    (net (code "58") (name "Net-(U3-3)") (class "Default")
      (node (ref "N1") (pin "3") (pinfunction "3_3") (pintype "bidirectional"))
      (node (ref "U3") (pin "9") (pinfunction "3_9") (pintype "bidirectional"))
    )
    (net (code "59") (name "Net-(U3-4)") (class "Default")
      (node (ref "N1") (pin "4") (pinfunction "4_4") (pintype "bidirectional"))
      (node (ref "U3") (pin "13") (pinfunction "4_13") (pintype "bidirectional"))
    )
    (net (code "60") (name "Net-(U3-5)") (class "Default")
      (node (ref "N1") (pin "5") (pinfunction "5_5") (pintype "bidirectional"))
      (node (ref "U3") (pin "14") (pinfunction "5_14") (pintype "bidirectional"))
    )
    (net (code "61") (name "Net-(U3-6)") (class "Default")
      (node (ref "N1") (pin "6") (pinfunction "6_6") (pintype "bidirectional"))
      (node (ref "U3") (pin "11") (pinfunction "6_11") (pintype "bidirectional"))
    )
    (net (code "62") (name "Net-(U3-7)") (class "Default")
      (node (ref "N1") (pin "7") (pinfunction "7_7") (pintype "bidirectional"))
      (node (ref "U3") (pin "10") (pinfunction "7_10") (pintype "bidirectional"))
    )
    (net (code "63") (name "Net-(U3-8)") (class "Default")
      (node (ref "N1") (pin "8") (pinfunction "8_8") (pintype "bidirectional"))
      (node (ref "U3") (pin "1") (pinfunction "8_1") (pintype "bidirectional"))
    )
    (net (code "64") (name "Net-(U3-9)") (class "Default")
      (node (ref "N1") (pin "9") (pinfunction "9_9") (pintype "bidirectional"))
      (node (ref "U3") (pin "2") (pinfunction "9_2") (pintype "bidirectional"))
    )
    (net (code "65") (name "Net-(U4-0)") (class "Default")
      (node (ref "N2") (pin "0") (pinfunction "0_0") (pintype "bidirectional"))
      (node (ref "U4") (pin "16") (pinfunction "0_16") (pintype "bidirectional"))
    )
    (net (code "66") (name "Net-(U4-1)") (class "Default")
      (node (ref "N2") (pin "1") (pinfunction "1_1") (pintype "bidirectional"))
      (node (ref "U4") (pin "15") (pinfunction "1_15") (pintype "bidirectional"))
    )
    (net (code "67") (name "Net-(U4-2)") (class "Default")
      (node (ref "N2") (pin "2") (pinfunction "2_2") (pintype "bidirectional"))
      (node (ref "U4") (pin "8") (pinfunction "2_8") (pintype "bidirectional"))
    )
    (net (code "68") (name "Net-(U4-3)") (class "Default")
      (node (ref "N2") (pin "3") (pinfunction "3_3") (pintype "bidirectional"))
      (node (ref "U4") (pin "9") (pinfunction "3_9") (pintype "bidirectional"))
    )
    (net (code "69") (name "Net-(U4-4)") (class "Default")
      (node (ref "N2") (pin "4") (pinfunction "4_4") (pintype "bidirectional"))
      (node (ref "U4") (pin "13") (pinfunction "4_13") (pintype "bidirectional"))
    )
    (net (code "70") (name "Net-(U4-5)") (class "Default")
      (node (ref "N2") (pin "5") (pinfunction "5_5") (pintype "bidirectional"))
      (node (ref "U4") (pin "14") (pinfunction "5_14") (pintype "bidirectional"))
    )
    (net (code "71") (name "Net-(U4-6)") (class "Default")
      (node (ref "N2") (pin "6") (pinfunction "6_6") (pintype "bidirectional"))
      (node (ref "U4") (pin "11") (pinfunction "6_11") (pintype "bidirectional"))
    )
    (net (code "72") (name "Net-(U4-7)") (class "Default")
      (node (ref "N2") (pin "7") (pinfunction "7_7") (pintype "bidirectional"))
      (node (ref "U4") (pin "10") (pinfunction "7_10") (pintype "bidirectional"))
    )
    (net (code "73") (name "Net-(U4-8)") (class "Default")
      (node (ref "N2") (pin "8") (pinfunction "8_8") (pintype "bidirectional"))
      (node (ref "U4") (pin "1") (pinfunction "8_1") (pintype "bidirectional"))
    )
    (net (code "74") (name "Net-(U4-9)") (class "Default")
      (node (ref "N2") (pin "9") (pinfunction "9_9") (pintype "bidirectional"))
      (node (ref "U4") (pin "2") (pinfunction "9_2") (pintype "bidirectional"))
    )
    (net (code "75") (name "Net-(U5-0)") (class "Default")
      (node (ref "N3") (pin "0") (pinfunction "0_0") (pintype "bidirectional"))
      (node (ref "U5") (pin "16") (pinfunction "0_16") (pintype "bidirectional"))
    )
    (net (code "76") (name "Net-(U5-1)") (class "Default")
      (node (ref "N3") (pin "1") (pinfunction "1_1") (pintype "bidirectional"))
      (node (ref "U5") (pin "15") (pinfunction "1_15") (pintype "bidirectional"))
    )
    (net (code "77") (name "Net-(U5-2)") (class "Default")
      (node (ref "N3") (pin "2") (pinfunction "2_2") (pintype "bidirectional"))
      (node (ref "U5") (pin "8") (pinfunction "2_8") (pintype "bidirectional"))
    )
    (net (code "78") (name "Net-(U5-3)") (class "Default")
      (node (ref "N3") (pin "3") (pinfunction "3_3") (pintype "bidirectional"))
      (node (ref "U5") (pin "9") (pinfunction "3_9") (pintype "bidirectional"))
    )
    (net (code "79") (name "Net-(U5-4)") (class "Default")
      (node (ref "N3") (pin "4") (pinfunction "4_4") (pintype "bidirectional"))
      (node (ref "U5") (pin "13") (pinfunction "4_13") (pintype "bidirectional"))
    )
    (net (code "80") (name "Net-(U5-5)") (class "Default")
      (node (ref "N3") (pin "5") (pinfunction "5_5") (pintype "bidirectional"))
      (node (ref "U5") (pin "14") (pinfunction "5_14") (pintype "bidirectional"))
    )
    (net (code "81") (name "Net-(U5-6)") (class "Default")
      (node (ref "N3") (pin "6") (pinfunction "6_6") (pintype "bidirectional"))
      (node (ref "U5") (pin "11") (pinfunction "6_11") (pintype "bidirectional"))
    )
    (net (code "82") (name "Net-(U5-7)") (class "Default")
      (node (ref "N3") (pin "7") (pinfunction "7_7") (pintype "bidirectional"))
      (node (ref "U5") (pin "10") (pinfunction "7_10") (pintype "bidirectional"))
    )
    (net (code "83") (name "Net-(U5-8)") (class "Default")
      (node (ref "N3") (pin "8") (pinfunction "8_8") (pintype "bidirectional"))
      (node (ref "U5") (pin "1") (pinfunction "8_1") (pintype "bidirectional"))
    )
    (net (code "84") (name "Net-(U5-9)") (class "Default")
      (node (ref "N3") (pin "9") (pinfunction "9_9") (pintype "bidirectional"))
      (node (ref "U5") (pin "2") (pinfunction "9_2") (pintype "bidirectional"))
    )
    (net (code "85") (name "Net-(U6-0)") (class "Default")
      (node (ref "N4") (pin "0") (pinfunction "0_0") (pintype "bidirectional"))
      (node (ref "U6") (pin "16") (pinfunction "0_16") (pintype "bidirectional"))
    )
    (net (code "86") (name "Net-(U6-1)") (class "Default")
      (node (ref "N4") (pin "1") (pinfunction "1_1") (pintype "bidirectional"))
      (node (ref "U6") (pin "15") (pinfunction "1_15") (pintype "bidirectional"))
    )
    (net (code "87") (name "Net-(U6-2)") (class "Default")
      (node (ref "N4") (pin "2") (pinfunction "2_2") (pintype "bidirectional"))
      (node (ref "U6") (pin "8") (pinfunction "2_8") (pintype "bidirectional"))
    )
    (net (code "88") (name "Net-(U6-3)") (class "Default")
      (node (ref "N4") (pin "3") (pinfunction "3_3") (pintype "bidirectional"))
      (node (ref "U6") (pin "9") (pinfunction "3_9") (pintype "bidirectional"))
    )
    (net (code "89") (name "Net-(U6-4)") (class "Default")
      (node (ref "N4") (pin "4") (pinfunction "4_4") (pintype "bidirectional"))
      (node (ref "U6") (pin "13") (pinfunction "4_13") (pintype "bidirectional"))
    )
    (net (code "90") (name "Net-(U6-5)") (class "Default")
      (node (ref "N4") (pin "5") (pinfunction "5_5") (pintype "bidirectional"))
      (node (ref "U6") (pin "14") (pinfunction "5_14") (pintype "bidirectional"))
    )
    (net (code "91") (name "Net-(U6-6)") (class "Default")
      (node (ref "N4") (pin "6") (pinfunction "6_6") (pintype "bidirectional"))
      (node (ref "U6") (pin "11") (pinfunction "6_11") (pintype "bidirectional"))
    )
    (net (code "92") (name "Net-(U6-7)") (class "Default")
      (node (ref "N4") (pin "7") (pinfunction "7_7") (pintype "bidirectional"))
      (node (ref "U6") (pin "10") (pinfunction "7_10") (pintype "bidirectional"))
    )
    (net (code "93") (name "Net-(U6-8)") (class "Default")
      (node (ref "N4") (pin "8") (pinfunction "8_8") (pintype "bidirectional"))
      (node (ref "U6") (pin "1") (pinfunction "8_1") (pintype "bidirectional"))
    )
    (net (code "94") (name "Net-(U6-9)") (class "Default")
      (node (ref "N4") (pin "9") (pinfunction "9_9") (pintype "bidirectional"))
      (node (ref "U6") (pin "2") (pinfunction "9_2") (pintype "bidirectional"))
    )
    (net (code "95") (name "Net-(U8-VBAT)") (class "Default")
      (node (ref "BATTERY") (pin "TP") (pinfunction "TP_TP") (pintype "input"))
      (node (ref "BT1") (pin "+") (pinfunction "+_+") (pintype "passive"))
      (node (ref "U8") (pin "14") (pinfunction "VBAT_14") (pintype "power_in"))
    )
    (net (code "96") (name "Net-(U10-OUT)") (class "Default")
      (node (ref "C10") (pin "1") (pinfunction "1_1") (pintype "passive"))
      (node (ref "C11") (pin "1") (pinfunction "1_1") (pintype "passive"))
      (node (ref "C9") (pin "1") (pinfunction "1_1") (pintype "passive"))
      (node (ref "GPS_PWR") (pin "TP") (pinfunction "TP_TP") (pintype "input"))
      (node (ref "U10") (pin "5") (pinfunction "OUT_5") (pintype "output"))
      (node (ref "U11") (pin "4") (pinfunction "VCC_4") (pintype "power_in"))
      (node (ref "U11") (pin "5") (pinfunction "V_BCKP_5") (pintype "power_in"))
    )
    (net (code "97") (name "Net-(U11-RXD1)") (class "Default")
      (node (ref "R19") (pin "2") (pinfunction "2_2") (pintype "passive"))
      (node (ref "R20") (pin "2") (pinfunction "2_2") (pintype "passive"))
      (node (ref "RX") (pin "TP") (pinfunction "TP_TP") (pintype "input"))
      (node (ref "U11") (pin "1") (pinfunction "RXD1_1") (pintype "input"))
    )
    (net (code "98") (name "Net-(U12-SEL)") (class "Default")
      (node (ref "SJ1") (pin "2") (pinfunction "2_2") (pintype "passive"))
      (node (ref "U12") (pin "11") (pinfunction "SEL_11") (pintype "bidirectional"))
    )
    (net (code "99") (name "ONE") (class "Default")
      (node (ref "S1") (pin "10") (pinfunction "10_10") (pintype "passive"))
      (node (ref "U1") (pin "77") (pinfunction "(AD1)PA1_77") (pintype "bidirectional"))
    )
    (net (code "100") (name "PLUS_MINUS") (class "Default")
      (node (ref "S1") (pin "14") (pinfunction "14_14") (pintype "passive"))
      (node (ref "U1") (pin "73") (pinfunction "(AD5)PA5_73") (pintype "bidirectional"))
    )
    (net (code "101") (name "RST") (class "Default")
      (node (ref "C1") (pin "2") (pinfunction "2_2") (pintype "passive"))
      (node (ref "J2") (pin "5") (pinfunction "5_5") (pintype "passive"))
      (node (ref "R1") (pin "1") (pinfunction "1_1") (pintype "passive"))
      (node (ref "U1") (pin "30") (pinfunction "RESET_30") (pintype "input"))
    )
    (net (code "102") (name "RTC_INT") (class "Default")
      (node (ref "RTC_INT") (pin "TP") (pinfunction "TP_TP") (pintype "input"))
      (node (ref "U1") (pin "6") (pinfunction "(OC3B/INT4)PE4_6") (pintype "bidirectional"))
      (node (ref "U8") (pin "3") (pinfunction "SQW/~{INT}_3") (pintype "output"))
    )
    (net (code "103") (name "RXI") (class "Default")
      (node (ref "D1") (pin "C") (pinfunction "C_C") (pintype "passive"))
      (node (ref "J1") (pin "P$3") (pinfunction "RXI_P$3") (pintype "passive"))
      (node (ref "U1") (pin "3") (pinfunction "(TXD0)PE1_3") (pintype "bidirectional"))
      (node (ref "U2") (pin "3") (pinfunction "RXI_3") (pintype "bidirectional"))
    )
    (net (code "104") (name "SCK") (class "Default")
      (node (ref "J2") (pin "3") (pinfunction "3_3") (pintype "passive"))
      (node (ref "U1") (pin "20") (pinfunction "(SCK/PCINT1)PB1_20") (pintype "bidirectional"))
    )
    (net (code "105") (name "SCL") (class "Default")
      (node (ref "R18") (pin "1") (pinfunction "1_1") (pintype "passive"))
      (node (ref "SCL") (pin "TP") (pinfunction "TP_TP") (pintype "input"))
      (node (ref "U1") (pin "43") (pinfunction "(SCL/INT0)PD0_43") (pintype "bidirectional"))
      (node (ref "U8") (pin "16") (pinfunction "SCL_16") (pintype "input"))
    )
    (net (code "106") (name "SDA") (class "Default")
      (node (ref "R17") (pin "1") (pinfunction "1_1") (pintype "passive"))
      (node (ref "SDA") (pin "TP") (pinfunction "TP_TP") (pintype "input"))
      (node (ref "U1") (pin "44") (pinfunction "(SDA/INT1)PD1_44") (pintype "bidirectional"))
      (node (ref "U8") (pin "15") (pinfunction "SDA_15") (pintype "bidirectional"))
    )
    (net (code "107") (name "TIME_MODE") (class "Default")
      (node (ref "S1") (pin "15") (pinfunction "15_15") (pintype "passive"))
      (node (ref "U1") (pin "72") (pinfunction "(AD6)PA6_72") (pintype "bidirectional"))
    )
    (net (code "108") (name "TWO") (class "Default")
      (node (ref "S1") (pin "11") (pinfunction "11_11") (pintype "passive"))
      (node (ref "U1") (pin "76") (pinfunction "(AD2)PA2_76") (pintype "bidirectional"))
    )
    (net (code "109") (name "TXO") (class "Default")
      (node (ref "D2") (pin "C") (pinfunction "C_C") (pintype "passive"))
      (node (ref "J1") (pin "P$2") (pinfunction "TXO_P$2") (pintype "passive"))
      (node (ref "U1") (pin "2") (pinfunction "(RXD0/PCIN8)PE0_2") (pintype "bidirectional"))
      (node (ref "U2") (pin "2") (pinfunction "TXO_2") (pintype "bidirectional"))
    )
    (net (code "110") (name "VCCA") (class "Default")
      (node (ref "5V_ANALOG") (pin "TP") (pinfunction "TP_TP") (pintype "input"))
      (node (ref "PH1") (pin "1") (pinfunction "1_1") (pintype "passive"))
      (node (ref "U1") (pin "100") (pinfunction "AVCC_100") (pintype "power_in"))
      (node (ref "U1") (pin "98") (pinfunction "AREF_98") (pintype "bidirectional"))
      (node (ref "U14") (pin "3") (pinfunction "VO_3") (pintype "passive"))
    )
    (net (code "111") (name "VOUT") (class "Default")
      (node (ref "C13") (pin "1") (pinfunction "1_1") (pintype "passive"))
      (node (ref "C16") (pin "1") (pinfunction "1_1") (pintype "passive"))
      (node (ref "C17") (pin "1") (pinfunction "1_1") (pintype "passive"))
      (node (ref "C18") (pin "1") (pinfunction "1_1") (pintype "passive"))
      (node (ref "T3") (pin "10") (pinfunction "D_10") (pintype "passive"))
      (node (ref "T3") (pin "11") (pinfunction "D_11") (pintype "passive"))
      (node (ref "T3") (pin "12") (pinfunction "D_12") (pintype "passive"))
      (node (ref "T3") (pin "5") (pinfunction "D_5") (pintype "passive"))
      (node (ref "T3") (pin "6") (pinfunction "D_6") (pintype "passive"))
      (node (ref "T3") (pin "7") (pinfunction "D_7") (pintype "passive"))
      (node (ref "T3") (pin "8") (pinfunction "D_8") (pintype "passive"))
      (node (ref "T3") (pin "9") (pinfunction "D_9") (pintype "passive"))
      (node (ref "U12") (pin "16") (pinfunction "VBUS_16") (pintype "bidirectional"))
      (node (ref "U13") (pin "1") (pinfunction "VI_1") (pintype "input"))
      (node (ref "U14") (pin "1") (pinfunction "VI_1") (pintype "input"))
      (node (ref "U7") (pin "1") (pinfunction "VCC_1") (pintype "bidirectional"))
      (node (ref "VOUT") (pin "TP") (pinfunction "TP_TP") (pintype "input"))
    )
    (net (code "112") (name "V_USB") (class "Default")
      (node (ref "C15") (pin "1") (pinfunction "1_1") (pintype "passive"))
      (node (ref "J5") (pin "A4B9") (pinfunction "VBUS_A4B9") (pintype "power_in"))
      (node (ref "J5") (pin "B4A9") (pinfunction "VBUS_B4A9") (pintype "power_in"))
      (node (ref "SJ1") (pin "1") (pinfunction "1_1") (pintype "passive"))
      (node (ref "T3") (pin "1") (pinfunction "S_1") (pintype "passive"))
      (node (ref "T3") (pin "2") (pinfunction "S_2") (pintype "passive"))
      (node (ref "T3") (pin "3") (pinfunction "S_3") (pintype "passive"))
      (node (ref "U12") (pin "2") (pinfunction "VIN_2") (pintype "bidirectional"))
      (node (ref "V_USB") (pin "TP") (pinfunction "TP_TP") (pintype "input"))
    )
    (net (code "113") (name "unconnected-(J5-SBU1-PadA8)") (class "Default")
      (node (ref "J5") (pin "A8") (pinfunction "SBU1_A8") (pintype "bidirectional"))
    )
    (net (code "114") (name "unconnected-(J5-SBU2-PadB8)") (class "Default")
      (node (ref "J5") (pin "B8") (pinfunction "SBU2_B8") (pintype "bidirectional"))
    )
    (net (code "115") (name "unconnected-(U1-(ADC1)PF1-Pad96)") (class "Default")
      (node (ref "U1") (pin "96") (pinfunction "(ADC1)PF1_96") (pintype "bidirectional"))
    )
    (net (code "116") (name "unconnected-(U1-(ADC2)PF2-Pad95)") (class "Default")
      (node (ref "U1") (pin "95") (pinfunction "(ADC2)PF2_95") (pintype "bidirectional"))
    )
    (net (code "117") (name "unconnected-(U1-(ADC3)PF3-Pad94)") (class "Default")
      (node (ref "U1") (pin "94") (pinfunction "(ADC3)PF3_94") (pintype "bidirectional"))
    )
    (net (code "118") (name "unconnected-(U1-(ADC4{slash}TCK)PF4-Pad93)") (class "Default")
      (node (ref "U1") (pin "93") (pinfunction "(ADC4/TCK)PF4_93") (pintype "bidirectional"))
    )
    (net (code "119") (name "unconnected-(U1-(ADC5{slash}TMS)PF5-Pad92)") (class "Default")
      (node (ref "U1") (pin "92") (pinfunction "(ADC5/TMS)PF5_92") (pintype "bidirectional"))
    )
    (net (code "120") (name "unconnected-(U1-(ADC6{slash}TDO)PF6-Pad91)") (class "Default")
      (node (ref "U1") (pin "91") (pinfunction "(ADC6/TDO)PF6_91") (pintype "bidirectional"))
    )
    (net (code "121") (name "unconnected-(U1-(ADC7{slash}TDI)PF7-Pad90)") (class "Default")
      (node (ref "U1") (pin "90") (pinfunction "(ADC7/TDI)PF7_90") (pintype "bidirectional"))
    )
    (net (code "122") (name "unconnected-(U1-(CLKO{slash}ICP3{slash}INT7)PE7-Pad9)") (class "Default")
      (node (ref "U1") (pin "9") (pinfunction "(CLKO/ICP3/INT7)PE7_9") (pintype "bidirectional"))
    )
    (net (code "123") (name "unconnected-(U1-(ICP1)PD4-Pad47)") (class "Default")
      (node (ref "U1") (pin "47") (pinfunction "(ICP1)PD4_47") (pintype "bidirectional"))
    )
    (net (code "124") (name "unconnected-(U1-(OC0A{slash}OC1C{slash}PCINT7)PB7-Pad26)") (class "Default")
      (node (ref "U1") (pin "26") (pinfunction "(OC0A/OC1C/PCINT7)PB7_26") (pintype "bidirectional"))
    )
    (net (code "125") (name "unconnected-(U1-(OC1A{slash}PCINT5)PB5-Pad24)") (class "Default")
      (node (ref "U1") (pin "24") (pinfunction "(OC1A/PCINT5)PB5_24") (pintype "bidirectional"))
    )
    (net (code "126") (name "unconnected-(U1-(OC1B{slash}PCINT6)PB6-Pad25)") (class "Default")
      (node (ref "U1") (pin "25") (pinfunction "(OC1B/PCINT6)PB6_25") (pintype "bidirectional"))
    )
    (net (code "127") (name "unconnected-(U1-(OC2A{slash}PCINT4)PB4-Pad23)") (class "Default")
      (node (ref "U1") (pin "23") (pinfunction "(OC2A/PCINT4)PB4_23") (pintype "bidirectional"))
    )
    (net (code "128") (name "unconnected-(U1-(OC3A{slash}AIN1)PE3-Pad5)") (class "Default")
      (node (ref "U1") (pin "5") (pinfunction "(OC3A/AIN1)PE3_5") (pintype "bidirectional"))
    )
    (net (code "129") (name "unconnected-(U1-(OC3C{slash}INT5)PE5-Pad7)") (class "Default")
      (node (ref "U1") (pin "7") (pinfunction "(OC3C/INT5)PE5_7") (pintype "bidirectional"))
    )
    (net (code "130") (name "unconnected-(U1-(RD)PG1-Pad52)") (class "Default")
      (node (ref "U1") (pin "52") (pinfunction "(RD)PG1_52") (pintype "bidirectional"))
    )
    (net (code "131") (name "unconnected-(U1-(RXD1{slash}INT2)PD2-Pad45)") (class "Default")
      (node (ref "U1") (pin "45") (pinfunction "(RXD1/INT2)PD2_45") (pintype "bidirectional"))
    )
    (net (code "132") (name "unconnected-(U1-(SS{slash}PCINT0)PB0-Pad19)") (class "Default")
      (node (ref "U1") (pin "19") (pinfunction "(SS/PCINT0)PB0_19") (pintype "bidirectional"))
    )
    (net (code "133") (name "unconnected-(U1-(T0)PD7-Pad50)") (class "Default")
      (node (ref "U1") (pin "50") (pinfunction "(T0)PD7_50") (pintype "bidirectional"))
    )
    (net (code "134") (name "unconnected-(U1-(T1)PD6-Pad49)") (class "Default")
      (node (ref "U1") (pin "49") (pinfunction "(T1)PD6_49") (pintype "bidirectional"))
    )
    (net (code "135") (name "unconnected-(U1-(T3{slash}INT6)PE6-Pad8)") (class "Default")
      (node (ref "U1") (pin "8") (pinfunction "(T3/INT6)PE6_8") (pintype "bidirectional"))
    )
    (net (code "136") (name "unconnected-(U1-(TOSC1)PG4-Pad29)") (class "Default")
      (node (ref "U1") (pin "29") (pinfunction "(TOSC1)PG4_29") (pintype "bidirectional"))
    )
    (net (code "137") (name "unconnected-(U1-(TOSC2)PG3-Pad28)") (class "Default")
      (node (ref "U1") (pin "28") (pinfunction "(TOSC2)PG3_28") (pintype "bidirectional"))
    )
    (net (code "138") (name "unconnected-(U1-(TXD1{slash}INT3)PD3-Pad46)") (class "Default")
      (node (ref "U1") (pin "46") (pinfunction "(TXD1/INT3)PD3_46") (pintype "bidirectional"))
    )
    (net (code "139") (name "unconnected-(U1-(WR)PG0-Pad51)") (class "Default")
      (node (ref "U1") (pin "51") (pinfunction "(WR)PG0_51") (pintype "bidirectional"))
    )
    (net (code "140") (name "unconnected-(U1-(XCK0{slash}AIN0)PE2-Pad4)") (class "Default")
      (node (ref "U1") (pin "4") (pinfunction "(XCK0/AIN0)PE2_4") (pintype "bidirectional"))
    )
    (net (code "141") (name "unconnected-(U1-(XCK1)PD5-Pad48)") (class "Default")
      (node (ref "U1") (pin "48") (pinfunction "(XCK1)PD5_48") (pintype "bidirectional"))
    )
    (net (code "142") (name "unconnected-(U1-PH0(RXD2)-Pad12)") (class "Default")
      (node (ref "U1") (pin "12") (pinfunction "PH0(RXD2)_12") (pintype "bidirectional"))
    )
    (net (code "143") (name "unconnected-(U1-PH1(TXD2)-Pad13)") (class "Default")
      (node (ref "U1") (pin "13") (pinfunction "PH1(TXD2)_13") (pintype "bidirectional"))
    )
    (net (code "144") (name "unconnected-(U1-PH2(XCK2)-Pad14)") (class "Default")
      (node (ref "U1") (pin "14") (pinfunction "PH2(XCK2)_14") (pintype "bidirectional"))
    )
    (net (code "145") (name "unconnected-(U1-PH3(OC4A)-Pad15)") (class "Default")
      (node (ref "U1") (pin "15") (pinfunction "PH3(OC4A)_15") (pintype "bidirectional"))
    )
    (net (code "146") (name "unconnected-(U1-PH4(OC4B)-Pad16)") (class "Default")
      (node (ref "U1") (pin "16") (pinfunction "PH4(OC4B)_16") (pintype "bidirectional"))
    )
    (net (code "147") (name "unconnected-(U1-PH5(OC4C)-Pad17)") (class "Default")
      (node (ref "U1") (pin "17") (pinfunction "PH5(OC4C)_17") (pintype "bidirectional"))
    )
    (net (code "148") (name "unconnected-(U1-PH6(OC2B)-Pad18)") (class "Default")
      (node (ref "U1") (pin "18") (pinfunction "PH6(OC2B)_18") (pintype "bidirectional"))
    )
    (net (code "149") (name "unconnected-(U1-PH7(T4)-Pad27)") (class "Default")
      (node (ref "U1") (pin "27") (pinfunction "PH7(T4)_27") (pintype "bidirectional"))
    )
    (net (code "150") (name "unconnected-(U1-PJ2(XCK3{slash}PCINT11)-Pad65)") (class "Default")
      (node (ref "U1") (pin "65") (pinfunction "PJ2(XCK3/PCINT11)_65") (pintype "bidirectional"))
    )
    (net (code "151") (name "unconnected-(U1-PJ3(PCINT12)-Pad66)") (class "Default")
      (node (ref "U1") (pin "66") (pinfunction "PJ3(PCINT12)_66") (pintype "bidirectional"))
    )
    (net (code "152") (name "unconnected-(U1-PJ4(PCINT13)-Pad67)") (class "Default")
      (node (ref "U1") (pin "67") (pinfunction "PJ4(PCINT13)_67") (pintype "bidirectional"))
    )
    (net (code "153") (name "unconnected-(U1-PJ5(PCINT14)-Pad68)") (class "Default")
      (node (ref "U1") (pin "68") (pinfunction "PJ5(PCINT14)_68") (pintype "bidirectional"))
    )
    (net (code "154") (name "unconnected-(U1-PJ6(PCINT15)-Pad69)") (class "Default")
      (node (ref "U1") (pin "69") (pinfunction "PJ6(PCINT15)_69") (pintype "bidirectional"))
    )
    (net (code "155") (name "unconnected-(U1-PJ7-Pad79)") (class "Default")
      (node (ref "U1") (pin "79") (pinfunction "PJ7_79") (pintype "bidirectional"))
    )
    (net (code "156") (name "unconnected-(U1-PK0(ADC8{slash}PCINT16)-Pad89)") (class "Default")
      (node (ref "U1") (pin "89") (pinfunction "PK0(ADC8/PCINT16)_89") (pintype "bidirectional"))
    )
    (net (code "157") (name "unconnected-(U1-PK1(ADC9{slash}PCINT17)-Pad88)") (class "Default")
      (node (ref "U1") (pin "88") (pinfunction "PK1(ADC9/PCINT17)_88") (pintype "bidirectional"))
    )
    (net (code "158") (name "unconnected-(U1-PK2(ADC10{slash}PCINT18)-Pad87)") (class "Default")
      (node (ref "U1") (pin "87") (pinfunction "PK2(ADC10/PCINT18)_87") (pintype "bidirectional"))
    )
    (net (code "159") (name "unconnected-(U1-PK3(ADC11{slash}PCINT19)-Pad86)") (class "Default")
      (node (ref "U1") (pin "86") (pinfunction "PK3(ADC11/PCINT19)_86") (pintype "bidirectional"))
    )
    (net (code "160") (name "unconnected-(U1-PK4(ADC12{slash}PCINT20)-Pad85)") (class "Default")
      (node (ref "U1") (pin "85") (pinfunction "PK4(ADC12/PCINT20)_85") (pintype "bidirectional"))
    )
    (net (code "161") (name "unconnected-(U1-PK5(ADC13{slash}PCINT21)-Pad84)") (class "Default")
      (node (ref "U1") (pin "84") (pinfunction "PK5(ADC13/PCINT21)_84") (pintype "bidirectional"))
    )
    (net (code "162") (name "unconnected-(U1-PK6(ADC14{slash}PCINT22)-Pad83)") (class "Default")
      (node (ref "U1") (pin "83") (pinfunction "PK6(ADC14/PCINT22)_83") (pintype "bidirectional"))
    )
    (net (code "163") (name "unconnected-(U1-PK7(ADC15{slash}PCINT23)-Pad82)") (class "Default")
      (node (ref "U1") (pin "82") (pinfunction "PK7(ADC15/PCINT23)_82") (pintype "bidirectional"))
    )
    (net (code "164") (name "unconnected-(U2-~{CTS}-Pad9)") (class "Default")
      (node (ref "U2") (pin "9") (pinfunction "~{CTS}_9") (pintype "bidirectional"))
    )
    (net (code "165") (name "unconnected-(U2-~{DCD}-Pad12)") (class "Default")
      (node (ref "U2") (pin "12") (pinfunction "~{DCD}_12") (pintype "bidirectional"))
    )
    (net (code "166") (name "unconnected-(U2-~{DSR}-Pad10)") (class "Default")
      (node (ref "U2") (pin "10") (pinfunction "~{DSR}_10") (pintype "bidirectional"))
    )
    (net (code "167") (name "unconnected-(U2-~{RI}-Pad11)") (class "Default")
      (node (ref "U2") (pin "11") (pinfunction "~{RI}_11") (pintype "bidirectional"))
    )
    (net (code "168") (name "unconnected-(U2-~{RTS}-Pad14)") (class "Default")
      (node (ref "U2") (pin "14") (pinfunction "~{RTS}_14") (pintype "bidirectional"))
    )
    (net (code "169") (name "unconnected-(U8-32KHZ-Pad1)") (class "Default")
      (node (ref "U8") (pin "1") (pinfunction "32KHZ_1") (pintype "output"))
    )
    (net (code "170") (name "unconnected-(U8-~{RST}-Pad4)") (class "Default")
      (node (ref "U8") (pin "4") (pinfunction "~{RST}_4") (pintype "input"))
    )
    (net (code "171") (name "unconnected-(U11-1PPS-Pad6)") (class "Default")
      (node (ref "U11") (pin "6") (pinfunction "1PPS_6") (pintype "output"))
    )
    (net (code "172") (name "unconnected-(U11-AADET_N-Pad8)") (class "Default")
      (node (ref "U11") (pin "8") (pinfunction "AADET_N_8") (pintype "bidirectional"))
    )
    (net (code "173") (name "unconnected-(U11-EX_ANT-Pad11)") (class "Default")
      (node (ref "U11") (pin "11") (pinfunction "EX_ANT_11") (pintype "input"))
    )
    (net (code "174") (name "unconnected-(U11-RESET-Pad10)") (class "Default")
      (node (ref "U11") (pin "10") (pinfunction "RESET_10") (pintype "input"))
    )
    (net (code "175") (name "unconnected-(U11-TIMER-Pad7)") (class "Default")
      (node (ref "U11") (pin "7") (pinfunction "TIMER_7") (pintype "output"))
    )
  )
)
